# ControlBoard.net
KiCad netlist of a schematic drawn in EAGLE
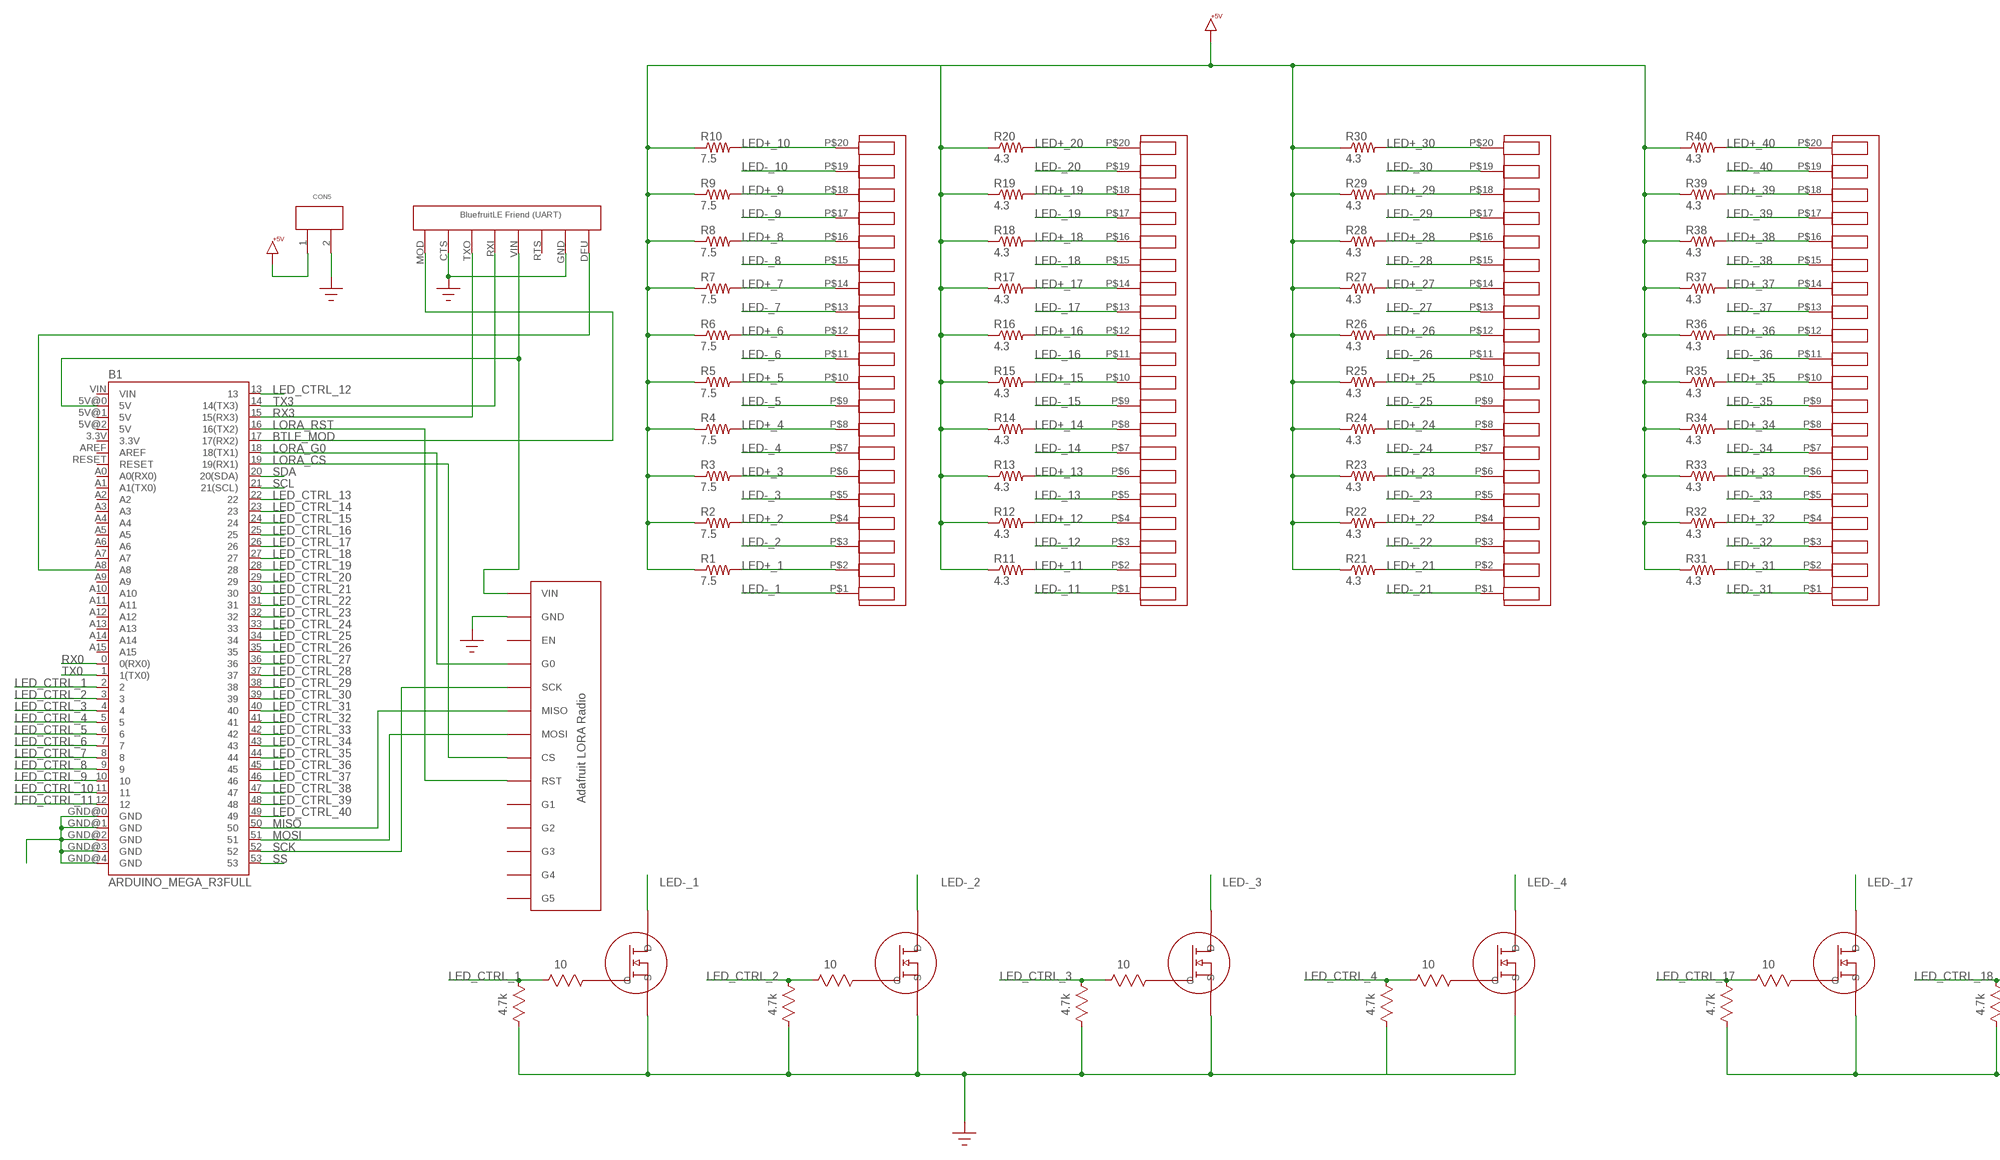
[diagram p0: schematic, sheet 1, part 1 of 3]
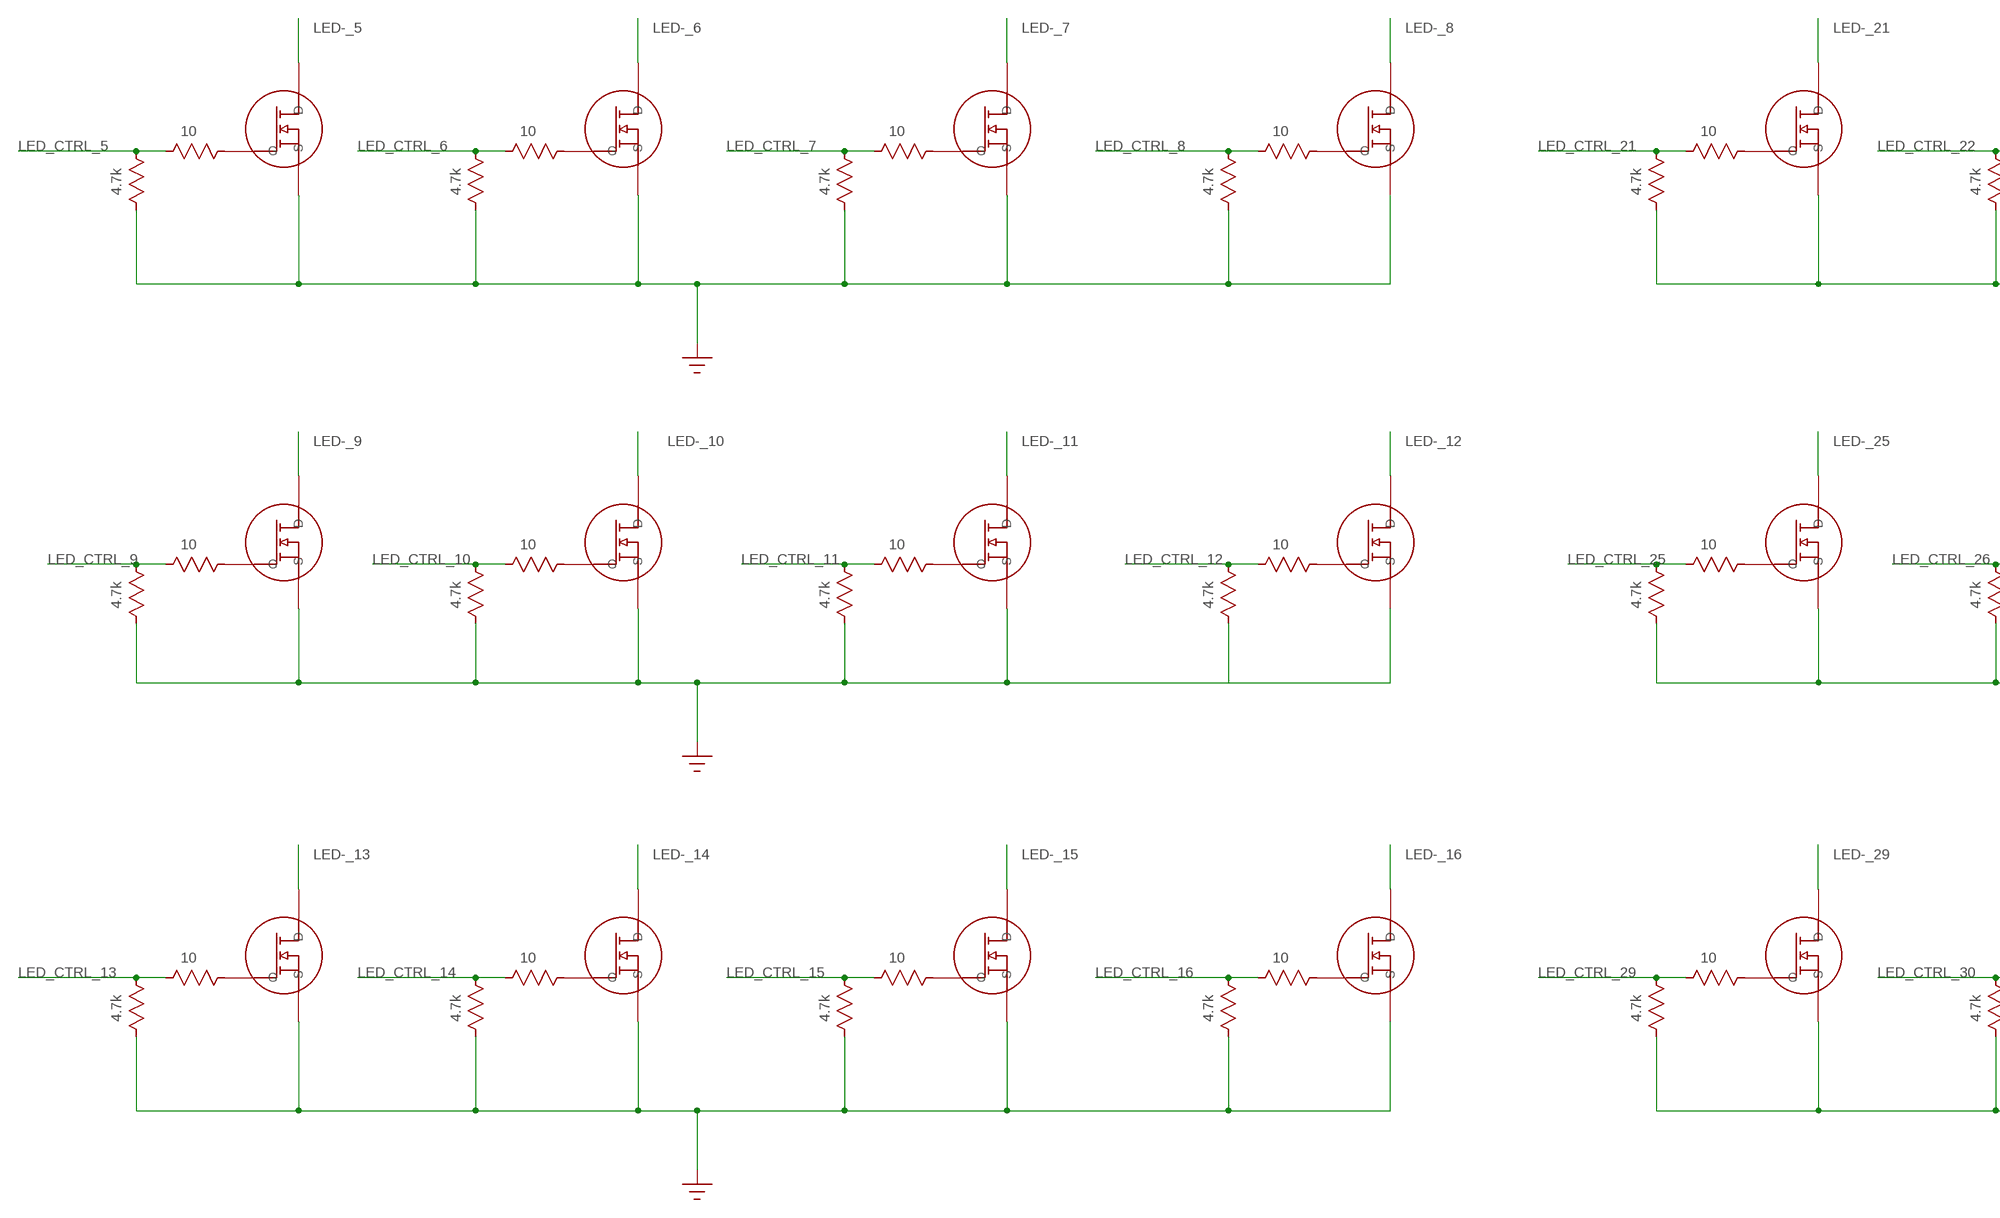
[diagram p1: schematic, sheet 1, part 2 of 3]
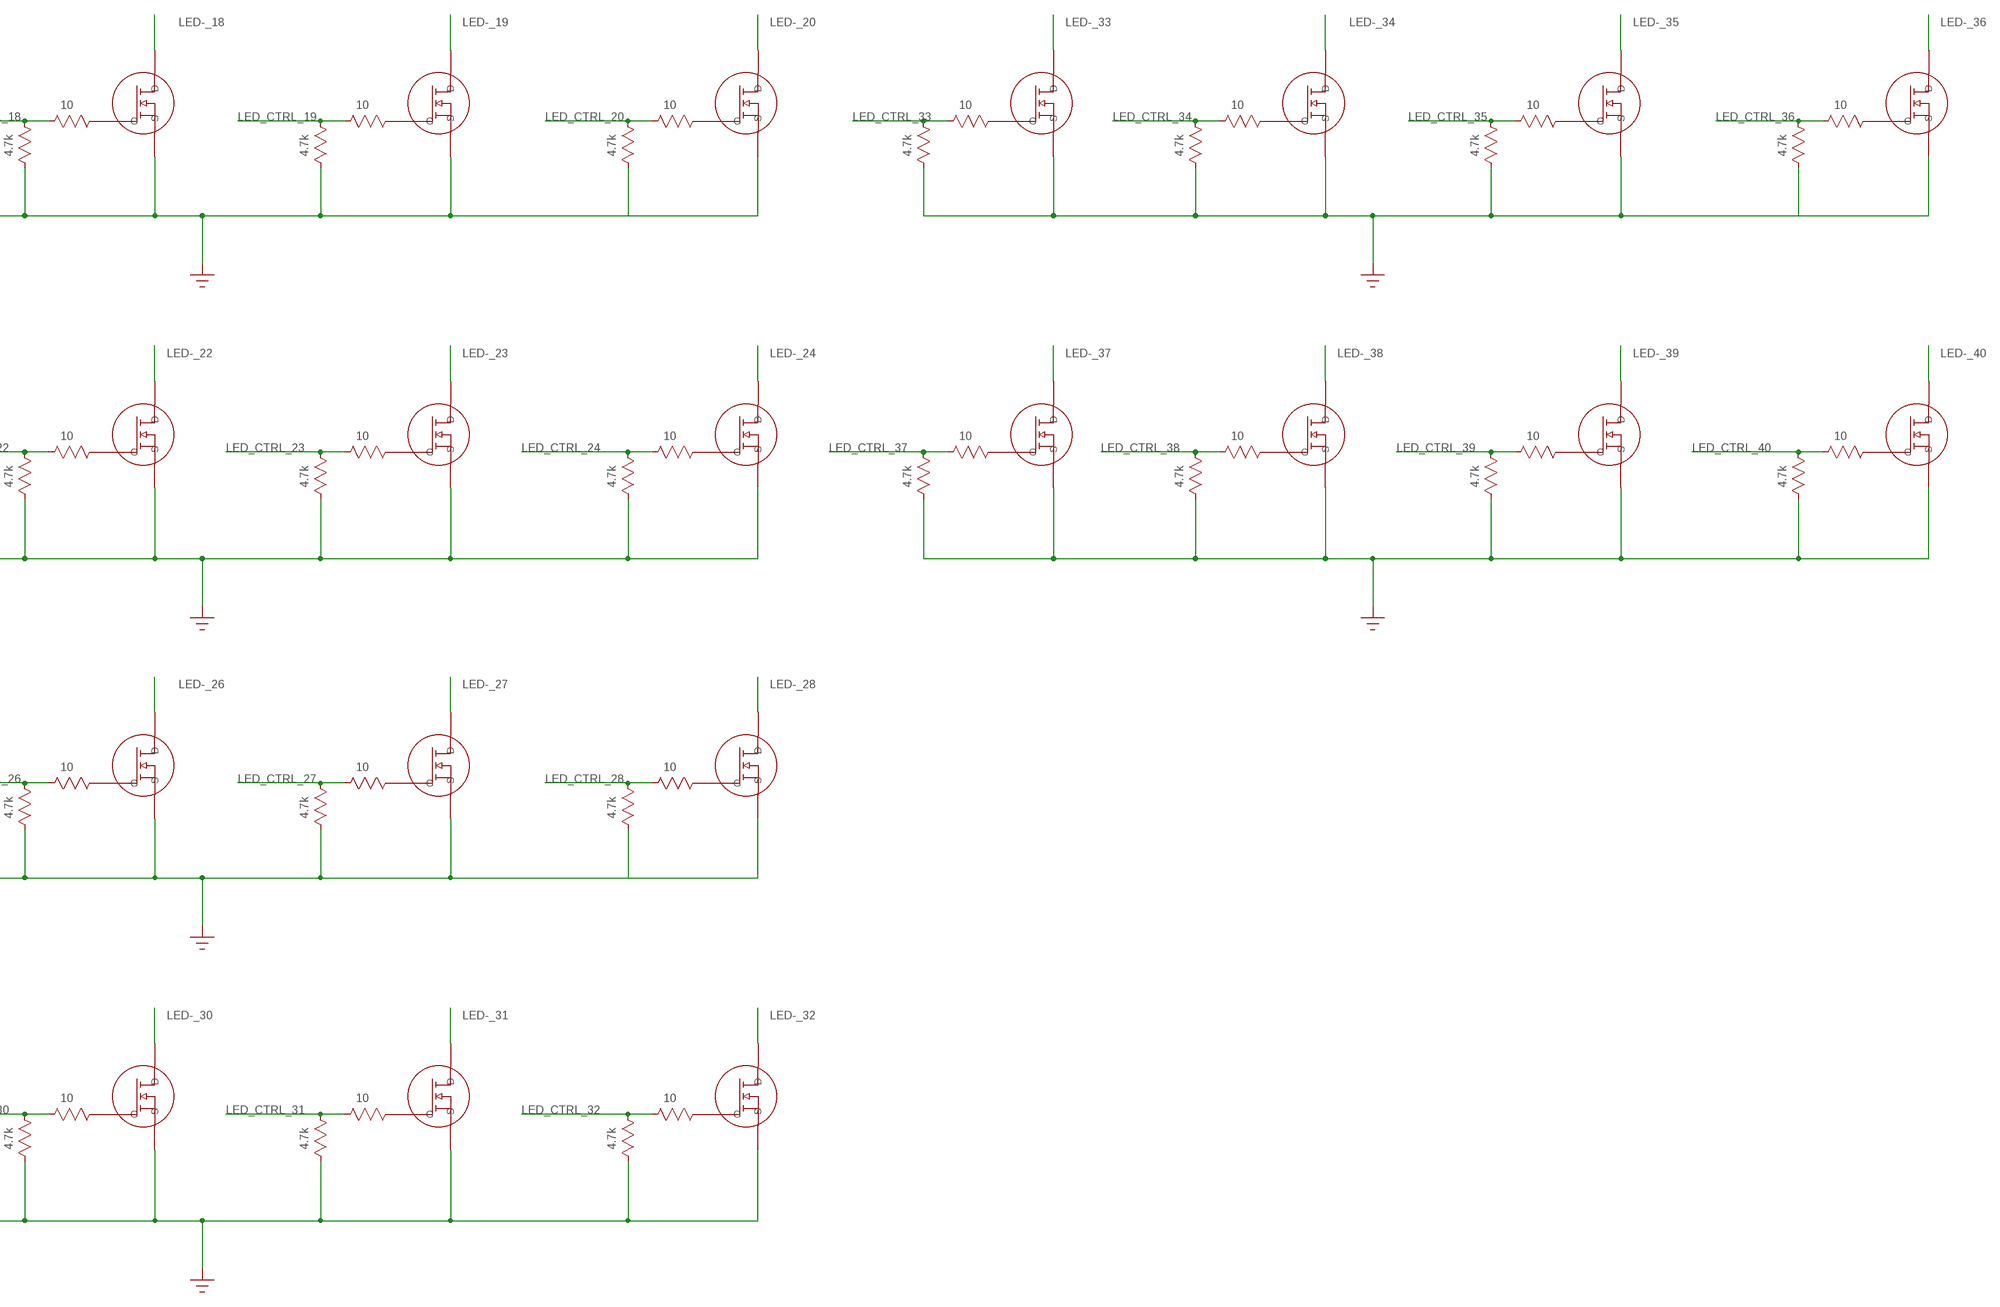
[diagram p2: schematic, sheet 1, part 3 of 3]

(export (version "E")
  (design (tool "Eeschema 10.0.6"))
  (components
    (comp (ref "B1")
      (value "ARDUINO_MEGA_R3FULL")
      (footprint "eagle-import:ARDUINO_MEGA")
      (libsource (lib "eagle-import") (part "ARDUINO_MEGA_R3FULL"))
    )
    (comp (ref "CON1")
      (value "CONN_20")
      (footprint "eagle-import:SPRING_CAGE_X20_1990180")
      (libsource (lib "eagle-import") (part "CONN_20"))
    )
    (comp (ref "CON2")
      (value "CONN_20")
      (footprint "eagle-import:SPRING_CAGE_X20_1990180")
      (libsource (lib "eagle-import") (part "CONN_20"))
    )
    (comp (ref "CON3")
      (value "CONN_20")
      (footprint "eagle-import:SPRING_CAGE_X20_1990180")
      (libsource (lib "eagle-import") (part "CONN_20"))
    )
    (comp (ref "CON4")
      (value "CONN_20")
      (footprint "eagle-import:SPRING_CAGE_X20_1990180")
      (libsource (lib "eagle-import") (part "CONN_20"))
    )
    (comp (ref "CON5")
      (value "CONN_2")
      (footprint "eagle-import:TERMINAL_BLOCK-2X_1792229")
      (libsource (lib "eagle-import") (part "CONN_2"))
    )
    (comp (ref "R1")
      (value "7.5")
      (footprint "eagle-import:RADIAL-RES-2W")
      (libsource (lib "eagle-import") (part "RESISTORPTH-2W_RADIAL"))
    )
    (comp (ref "R2")
      (value "7.5")
      (footprint "eagle-import:RADIAL-RES-2W")
      (libsource (lib "eagle-import") (part "RESISTORPTH-2W_RADIAL"))
    )
    (comp (ref "R3")
      (value "7.5")
      (footprint "eagle-import:RADIAL-RES-2W")
      (libsource (lib "eagle-import") (part "RESISTORPTH-2W_RADIAL"))
    )
    (comp (ref "R4")
      (value "7.5")
      (footprint "eagle-import:RADIAL-RES-2W")
      (libsource (lib "eagle-import") (part "RESISTORPTH-2W_RADIAL"))
    )
    (comp (ref "R5")
      (value "7.5")
      (footprint "eagle-import:RADIAL-RES-2W")
      (libsource (lib "eagle-import") (part "RESISTORPTH-2W_RADIAL"))
    )
    (comp (ref "R6")
      (value "7.5")
      (footprint "eagle-import:RADIAL-RES-2W")
      (libsource (lib "eagle-import") (part "RESISTORPTH-2W_RADIAL"))
    )
    (comp (ref "R7")
      (value "7.5")
      (footprint "eagle-import:RADIAL-RES-2W")
      (libsource (lib "eagle-import") (part "RESISTORPTH-2W_RADIAL"))
    )
    (comp (ref "R8")
      (value "7.5")
      (footprint "eagle-import:RADIAL-RES-2W")
      (libsource (lib "eagle-import") (part "RESISTORPTH-2W_RADIAL"))
    )
    (comp (ref "R9")
      (value "7.5")
      (footprint "eagle-import:RADIAL-RES-2W")
      (libsource (lib "eagle-import") (part "RESISTORPTH-2W_RADIAL"))
    )
    (comp (ref "R10")
      (value "7.5")
      (footprint "eagle-import:RADIAL-RES-2W")
      (libsource (lib "eagle-import") (part "RESISTORPTH-2W_RADIAL"))
    )
    (comp (ref "R11")
      (value "4.3")
      (footprint "eagle-import:RADIAL-RES-2W")
      (libsource (lib "eagle-import") (part "RESISTORPTH-2W_RADIAL"))
    )
    (comp (ref "R12")
      (value "4.3")
      (footprint "eagle-import:RADIAL-RES-2W")
      (libsource (lib "eagle-import") (part "RESISTORPTH-2W_RADIAL"))
    )
    (comp (ref "R13")
      (value "4.3")
      (footprint "eagle-import:RADIAL-RES-2W")
      (libsource (lib "eagle-import") (part "RESISTORPTH-2W_RADIAL"))
    )
    (comp (ref "R14")
      (value "4.3")
      (footprint "eagle-import:RADIAL-RES-2W")
      (libsource (lib "eagle-import") (part "RESISTORPTH-2W_RADIAL"))
    )
    (comp (ref "R15")
      (value "4.3")
      (footprint "eagle-import:RADIAL-RES-2W")
      (libsource (lib "eagle-import") (part "RESISTORPTH-2W_RADIAL"))
    )
    (comp (ref "R16")
      (value "4.3")
      (footprint "eagle-import:RADIAL-RES-2W")
      (libsource (lib "eagle-import") (part "RESISTORPTH-2W_RADIAL"))
    )
    (comp (ref "R17")
      (value "4.3")
      (footprint "eagle-import:RADIAL-RES-2W")
      (libsource (lib "eagle-import") (part "RESISTORPTH-2W_RADIAL"))
    )
    (comp (ref "R18")
      (value "4.3")
      (footprint "eagle-import:RADIAL-RES-2W")
      (libsource (lib "eagle-import") (part "RESISTORPTH-2W_RADIAL"))
    )
    (comp (ref "R19")
      (value "4.3")
      (footprint "eagle-import:RADIAL-RES-2W")
      (libsource (lib "eagle-import") (part "RESISTORPTH-2W_RADIAL"))
    )
    (comp (ref "R20")
      (value "4.3")
      (footprint "eagle-import:RADIAL-RES-2W")
      (libsource (lib "eagle-import") (part "RESISTORPTH-2W_RADIAL"))
    )
    (comp (ref "R21")
      (value "4.3")
      (footprint "eagle-import:RADIAL-RES-2W")
      (libsource (lib "eagle-import") (part "RESISTORPTH-2W_RADIAL"))
    )
    (comp (ref "R22")
      (value "4.3")
      (footprint "eagle-import:RADIAL-RES-2W")
      (libsource (lib "eagle-import") (part "RESISTORPTH-2W_RADIAL"))
    )
    (comp (ref "R23")
      (value "4.3")
      (footprint "eagle-import:RADIAL-RES-2W")
      (libsource (lib "eagle-import") (part "RESISTORPTH-2W_RADIAL"))
    )
    (comp (ref "R24")
      (value "4.3")
      (footprint "eagle-import:RADIAL-RES-2W")
      (libsource (lib "eagle-import") (part "RESISTORPTH-2W_RADIAL"))
    )
    (comp (ref "R25")
      (value "4.3")
      (footprint "eagle-import:RADIAL-RES-2W")
      (libsource (lib "eagle-import") (part "RESISTORPTH-2W_RADIAL"))
    )
    (comp (ref "R26")
      (value "4.3")
      (footprint "eagle-import:RADIAL-RES-2W")
      (libsource (lib "eagle-import") (part "RESISTORPTH-2W_RADIAL"))
    )
    (comp (ref "R27")
      (value "4.3")
      (footprint "eagle-import:RADIAL-RES-2W")
      (libsource (lib "eagle-import") (part "RESISTORPTH-2W_RADIAL"))
    )
    (comp (ref "R28")
      (value "4.3")
      (footprint "eagle-import:RADIAL-RES-2W")
      (libsource (lib "eagle-import") (part "RESISTORPTH-2W_RADIAL"))
    )
    (comp (ref "R29")
      (value "4.3")
      (footprint "eagle-import:RADIAL-RES-2W")
      (libsource (lib "eagle-import") (part "RESISTORPTH-2W_RADIAL"))
    )
    (comp (ref "R30")
      (value "4.3")
      (footprint "eagle-import:RADIAL-RES-2W")
      (libsource (lib "eagle-import") (part "RESISTORPTH-2W_RADIAL"))
    )
    (comp (ref "R31")
      (value "4.3")
      (footprint "eagle-import:RADIAL-RES-2W")
      (libsource (lib "eagle-import") (part "RESISTORPTH-2W_RADIAL"))
    )
    (comp (ref "R32")
      (value "4.3")
      (footprint "eagle-import:RADIAL-RES-2W")
      (libsource (lib "eagle-import") (part "RESISTORPTH-2W_RADIAL"))
    )
    (comp (ref "R33")
      (value "4.3")
      (footprint "eagle-import:RADIAL-RES-2W")
      (libsource (lib "eagle-import") (part "RESISTORPTH-2W_RADIAL"))
    )
    (comp (ref "R34")
      (value "4.3")
      (footprint "eagle-import:RADIAL-RES-2W")
      (libsource (lib "eagle-import") (part "RESISTORPTH-2W_RADIAL"))
    )
    (comp (ref "R35")
      (value "4.3")
      (footprint "eagle-import:RADIAL-RES-2W")
      (libsource (lib "eagle-import") (part "RESISTORPTH-2W_RADIAL"))
    )
    (comp (ref "R36")
      (value "4.3")
      (footprint "eagle-import:RADIAL-RES-2W")
      (libsource (lib "eagle-import") (part "RESISTORPTH-2W_RADIAL"))
    )
    (comp (ref "R37")
      (value "4.3")
      (footprint "eagle-import:RADIAL-RES-2W")
      (libsource (lib "eagle-import") (part "RESISTORPTH-2W_RADIAL"))
    )
    (comp (ref "R38")
      (value "4.3")
      (footprint "eagle-import:RADIAL-RES-2W")
      (libsource (lib "eagle-import") (part "RESISTORPTH-2W_RADIAL"))
    )
    (comp (ref "R39")
      (value "4.3")
      (footprint "eagle-import:RADIAL-RES-2W")
      (libsource (lib "eagle-import") (part "RESISTORPTH-2W_RADIAL"))
    )
    (comp (ref "R40")
      (value "4.3")
      (footprint "eagle-import:RADIAL-RES-2W")
      (libsource (lib "eagle-import") (part "RESISTORPTH-2W_RADIAL"))
    )
    (comp (ref "R41")
      (value "4.7k")
      (footprint "eagle-import:1506_X8")
      (libsource (lib "eagle-import") (part "RESISTOR_X8"))
    )
    (comp (ref "R42")
      (value "4.7k")
      (footprint "eagle-import:1506_X8")
      (libsource (lib "eagle-import") (part "RESISTOR_X8"))
    )
    (comp (ref "R43")
      (value "4.7k")
      (footprint "eagle-import:1506_X8")
      (libsource (lib "eagle-import") (part "RESISTOR_X8"))
    )
    (comp (ref "R44")
      (value "4.7k")
      (footprint "eagle-import:1506_X8")
      (libsource (lib "eagle-import") (part "RESISTOR_X8"))
    )
    (comp (ref "R45")
      (value "4.7k")
      (footprint "eagle-import:1506_X8")
      (libsource (lib "eagle-import") (part "RESISTOR_X8"))
    )
    (comp (ref "R46")
      (value "10")
      (footprint "eagle-import:1506_X8")
      (libsource (lib "eagle-import") (part "RESISTOR_X8"))
    )
    (comp (ref "R47")
      (value "10")
      (footprint "eagle-import:1506_X8")
      (libsource (lib "eagle-import") (part "RESISTOR_X8"))
    )
    (comp (ref "R48")
      (value "10")
      (footprint "eagle-import:1506_X8")
      (libsource (lib "eagle-import") (part "RESISTOR_X8"))
    )
    (comp (ref "R49")
      (value "10")
      (footprint "eagle-import:1506_X8")
      (libsource (lib "eagle-import") (part "RESISTOR_X8"))
    )
    (comp (ref "R50")
      (value "10")
      (footprint "eagle-import:1506_X8")
      (libsource (lib "eagle-import") (part "RESISTOR_X8"))
    )
    (comp (ref "U$1")
      (value "MOSFET")
      (footprint "eagle-import:SOT-23_TO-236")
      (libsource (lib "eagle-import") (part "MOSFET"))
    )
    (comp (ref "U$2")
      (value "MOSFET")
      (footprint "eagle-import:SOT-23_TO-236")
      (libsource (lib "eagle-import") (part "MOSFET"))
    )
    (comp (ref "U$3")
      (value "MOSFET")
      (footprint "eagle-import:SOT-23_TO-236")
      (libsource (lib "eagle-import") (part "MOSFET"))
    )
    (comp (ref "U$4")
      (value "MOSFET")
      (footprint "eagle-import:SOT-23_TO-236")
      (libsource (lib "eagle-import") (part "MOSFET"))
    )
    (comp (ref "U$5")
      (value "MOSFET")
      (footprint "eagle-import:SOT-23_TO-236")
      (libsource (lib "eagle-import") (part "MOSFET"))
    )
    (comp (ref "U$6")
      (value "MOSFET")
      (footprint "eagle-import:SOT-23_TO-236")
      (libsource (lib "eagle-import") (part "MOSFET"))
    )
    (comp (ref "U$7")
      (value "MOSFET")
      (footprint "eagle-import:SOT-23_TO-236")
      (libsource (lib "eagle-import") (part "MOSFET"))
    )
    (comp (ref "U$8")
      (value "MOSFET")
      (footprint "eagle-import:SOT-23_TO-236")
      (libsource (lib "eagle-import") (part "MOSFET"))
    )
    (comp (ref "U$9")
      (value "MOSFET")
      (footprint "eagle-import:SOT-23_TO-236")
      (libsource (lib "eagle-import") (part "MOSFET"))
    )
    (comp (ref "U$10")
      (value "MOSFET")
      (footprint "eagle-import:SOT-23_TO-236")
      (libsource (lib "eagle-import") (part "MOSFET"))
    )
    (comp (ref "U$15")
      (value "MOSFET")
      (footprint "eagle-import:SOT-23_TO-236")
      (libsource (lib "eagle-import") (part "MOSFET"))
    )
    (comp (ref "U$16")
      (value "MOSFET")
      (footprint "eagle-import:SOT-23_TO-236")
      (libsource (lib "eagle-import") (part "MOSFET"))
    )
    (comp (ref "U$17")
      (value "MOSFET")
      (footprint "eagle-import:SOT-23_TO-236")
      (libsource (lib "eagle-import") (part "MOSFET"))
    )
    (comp (ref "U$18")
      (value "MOSFET")
      (footprint "eagle-import:SOT-23_TO-236")
      (libsource (lib "eagle-import") (part "MOSFET"))
    )
    (comp (ref "U$19")
      (value "MOSFET")
      (footprint "eagle-import:SOT-23_TO-236")
      (libsource (lib "eagle-import") (part "MOSFET"))
    )
    (comp (ref "U$20")
      (value "MOSFET")
      (footprint "eagle-import:SOT-23_TO-236")
      (libsource (lib "eagle-import") (part "MOSFET"))
    )
    (comp (ref "U$21")
      (value "MOSFET")
      (footprint "eagle-import:SOT-23_TO-236")
      (libsource (lib "eagle-import") (part "MOSFET"))
    )
    (comp (ref "U$22")
      (value "MOSFET")
      (footprint "eagle-import:SOT-23_TO-236")
      (libsource (lib "eagle-import") (part "MOSFET"))
    )
    (comp (ref "U$27")
      (value "MOSFET")
      (footprint "eagle-import:SOT-23_TO-236")
      (libsource (lib "eagle-import") (part "MOSFET"))
    )
    (comp (ref "U$28")
      (value "MOSFET")
      (footprint "eagle-import:SOT-23_TO-236")
      (libsource (lib "eagle-import") (part "MOSFET"))
    )
    (comp (ref "U$29")
      (value "MOSFET")
      (footprint "eagle-import:SOT-23_TO-236")
      (libsource (lib "eagle-import") (part "MOSFET"))
    )
    (comp (ref "U$30")
      (value "MOSFET")
      (footprint "eagle-import:SOT-23_TO-236")
      (libsource (lib "eagle-import") (part "MOSFET"))
    )
    (comp (ref "U$31")
      (value "MOSFET")
      (footprint "eagle-import:SOT-23_TO-236")
      (libsource (lib "eagle-import") (part "MOSFET"))
    )
    (comp (ref "U$32")
      (value "MOSFET")
      (footprint "eagle-import:SOT-23_TO-236")
      (libsource (lib "eagle-import") (part "MOSFET"))
    )
    (comp (ref "U$37")
      (value "MOSFET")
      (footprint "eagle-import:SOT-23_TO-236")
      (libsource (lib "eagle-import") (part "MOSFET"))
    )
    (comp (ref "U$38")
      (value "MOSFET")
      (footprint "eagle-import:SOT-23_TO-236")
      (libsource (lib "eagle-import") (part "MOSFET"))
    )
    (comp (ref "U$39")
      (value "MOSFET")
      (footprint "eagle-import:SOT-23_TO-236")
      (libsource (lib "eagle-import") (part "MOSFET"))
    )
    (comp (ref "U$40")
      (value "MOSFET")
      (footprint "eagle-import:SOT-23_TO-236")
      (libsource (lib "eagle-import") (part "MOSFET"))
    )
    (comp (ref "U$41")
      (value "MOSFET")
      (footprint "eagle-import:SOT-23_TO-236")
      (libsource (lib "eagle-import") (part "MOSFET"))
    )
    (comp (ref "U$42")
      (value "MOSFET")
      (footprint "eagle-import:SOT-23_TO-236")
      (libsource (lib "eagle-import") (part "MOSFET"))
    )
    (comp (ref "U$43")
      (value "MOSFET")
      (footprint "eagle-import:SOT-23_TO-236")
      (libsource (lib "eagle-import") (part "MOSFET"))
    )
    (comp (ref "U$44")
      (value "MOSFET")
      (footprint "eagle-import:SOT-23_TO-236")
      (libsource (lib "eagle-import") (part "MOSFET"))
    )
    (comp (ref "U$49")
      (value "MOSFET")
      (footprint "eagle-import:SOT-23_TO-236")
      (libsource (lib "eagle-import") (part "MOSFET"))
    )
    (comp (ref "U$50")
      (value "MOSFET")
      (footprint "eagle-import:SOT-23_TO-236")
      (libsource (lib "eagle-import") (part "MOSFET"))
    )
    (comp (ref "U$51")
      (value "MOSFET")
      (footprint "eagle-import:SOT-23_TO-236")
      (libsource (lib "eagle-import") (part "MOSFET"))
    )
    (comp (ref "U$52")
      (value "MOSFET")
      (footprint "eagle-import:SOT-23_TO-236")
      (libsource (lib "eagle-import") (part "MOSFET"))
    )
    (comp (ref "U$53")
      (value "MOSFET")
      (footprint "eagle-import:SOT-23_TO-236")
      (libsource (lib "eagle-import") (part "MOSFET"))
    )
    (comp (ref "U$54")
      (value "MOSFET")
      (footprint "eagle-import:SOT-23_TO-236")
      (libsource (lib "eagle-import") (part "MOSFET"))
    )
    (comp (ref "U$55")
      (value "MOSFET")
      (footprint "eagle-import:SOT-23_TO-236")
      (libsource (lib "eagle-import") (part "MOSFET"))
    )
    (comp (ref "U$56")
      (value "MOSFET")
      (footprint "eagle-import:SOT-23_TO-236")
      (libsource (lib "eagle-import") (part "MOSFET"))
    )
    (comp (ref "U$62")
      (value "BLUEFRUIT_LE_FRIEND_UART")
      (footprint "eagle-import:BLUEFRUIT_LE_FRIEND_UART")
      (libsource (lib "eagle-import") (part "BLUEFRUIT_LE_FRIEND_UART"))
    )
    (comp (ref "U$64")
      (value "ADAFRUIT_LORA_RADIO")
      (footprint "eagle-import:ADAFRUIT_LORA_RADIO")
      (libsource (lib "eagle-import") (part "ADAFRUIT_LORA_RADIO"))
    )
  )
  (nets
    (net (code "1") (name "+5V") (class "Default")
      (node (ref "CON5") (pin "1") (pinfunction "P$1_1") (pintype "bidirectional"))
      (node (ref "R1") (pin "P$1") (pinfunction "1_P$1") (pintype "passive"))
      (node (ref "R10") (pin "P$1") (pinfunction "1_P$1") (pintype "passive"))
      (node (ref "R11") (pin "P$1") (pinfunction "1_P$1") (pintype "passive"))
      (node (ref "R12") (pin "P$1") (pinfunction "1_P$1") (pintype "passive"))
      (node (ref "R13") (pin "P$1") (pinfunction "1_P$1") (pintype "passive"))
      (node (ref "R14") (pin "P$1") (pinfunction "1_P$1") (pintype "passive"))
      (node (ref "R15") (pin "P$1") (pinfunction "1_P$1") (pintype "passive"))
      (node (ref "R16") (pin "P$1") (pinfunction "1_P$1") (pintype "passive"))
      (node (ref "R17") (pin "P$1") (pinfunction "1_P$1") (pintype "passive"))
      (node (ref "R18") (pin "P$1") (pinfunction "1_P$1") (pintype "passive"))
      (node (ref "R19") (pin "P$1") (pinfunction "1_P$1") (pintype "passive"))
      (node (ref "R2") (pin "P$1") (pinfunction "1_P$1") (pintype "passive"))
      (node (ref "R20") (pin "P$1") (pinfunction "1_P$1") (pintype "passive"))
      (node (ref "R21") (pin "P$1") (pinfunction "1_P$1") (pintype "passive"))
      (node (ref "R22") (pin "P$1") (pinfunction "1_P$1") (pintype "passive"))
      (node (ref "R23") (pin "P$1") (pinfunction "1_P$1") (pintype "passive"))
      (node (ref "R24") (pin "P$1") (pinfunction "1_P$1") (pintype "passive"))
      (node (ref "R25") (pin "P$1") (pinfunction "1_P$1") (pintype "passive"))
      (node (ref "R26") (pin "P$1") (pinfunction "1_P$1") (pintype "passive"))
      (node (ref "R27") (pin "P$1") (pinfunction "1_P$1") (pintype "passive"))
      (node (ref "R28") (pin "P$1") (pinfunction "1_P$1") (pintype "passive"))
      (node (ref "R29") (pin "P$1") (pinfunction "1_P$1") (pintype "passive"))
      (node (ref "R3") (pin "P$1") (pinfunction "1_P$1") (pintype "passive"))
      (node (ref "R30") (pin "P$1") (pinfunction "1_P$1") (pintype "passive"))
      (node (ref "R31") (pin "P$1") (pinfunction "1_P$1") (pintype "passive"))
      (node (ref "R32") (pin "P$1") (pinfunction "1_P$1") (pintype "passive"))
      (node (ref "R33") (pin "P$1") (pinfunction "1_P$1") (pintype "passive"))
      (node (ref "R34") (pin "P$1") (pinfunction "1_P$1") (pintype "passive"))
      (node (ref "R35") (pin "P$1") (pinfunction "1_P$1") (pintype "passive"))
      (node (ref "R36") (pin "P$1") (pinfunction "1_P$1") (pintype "passive"))
      (node (ref "R37") (pin "P$1") (pinfunction "1_P$1") (pintype "passive"))
      (node (ref "R38") (pin "P$1") (pinfunction "1_P$1") (pintype "passive"))
      (node (ref "R39") (pin "P$1") (pinfunction "1_P$1") (pintype "passive"))
      (node (ref "R4") (pin "P$1") (pinfunction "1_P$1") (pintype "passive"))
      (node (ref "R40") (pin "P$1") (pinfunction "1_P$1") (pintype "passive"))
      (node (ref "R5") (pin "P$1") (pinfunction "1_P$1") (pintype "passive"))
      (node (ref "R6") (pin "P$1") (pinfunction "1_P$1") (pintype "passive"))
      (node (ref "R7") (pin "P$1") (pinfunction "1_P$1") (pintype "passive"))
      (node (ref "R8") (pin "P$1") (pinfunction "1_P$1") (pintype "passive"))
      (node (ref "R9") (pin "P$1") (pinfunction "1_P$1") (pintype "passive"))
    )
    (net (code "2") (name "/BTLE_MOD") (class "Default")
      (node (ref "B1") (pin "17") (pinfunction "17(RX2)_17") (pintype "bidirectional"))
      (node (ref "U$62") (pin "MOD") (pinfunction "P$1_MOD") (pintype "bidirectional"))
    )
    (net (code "3") (name "/LED+_1") (class "Default")
      (node (ref "CON1") (pin "P$2") (pinfunction "2_P$2") (pintype "bidirectional"))
      (node (ref "R1") (pin "P$2") (pinfunction "2_P$2") (pintype "passive"))
    )
    (net (code "4") (name "/LED+_2") (class "Default")
      (node (ref "CON1") (pin "P$4") (pinfunction "4_P$4") (pintype "bidirectional"))
      (node (ref "R2") (pin "P$2") (pinfunction "2_P$2") (pintype "passive"))
    )
    (net (code "5") (name "/LED+_3") (class "Default")
      (node (ref "CON1") (pin "P$6") (pinfunction "6_P$6") (pintype "bidirectional"))
      (node (ref "R3") (pin "P$2") (pinfunction "2_P$2") (pintype "passive"))
    )
    (net (code "6") (name "/LED+_4") (class "Default")
      (node (ref "CON1") (pin "P$8") (pinfunction "8_P$8") (pintype "bidirectional"))
      (node (ref "R4") (pin "P$2") (pinfunction "2_P$2") (pintype "passive"))
    )
    (net (code "7") (name "/LED+_5") (class "Default")
      (node (ref "CON1") (pin "P$10") (pinfunction "10_P$10") (pintype "bidirectional"))
      (node (ref "R5") (pin "P$2") (pinfunction "2_P$2") (pintype "passive"))
    )
    (net (code "8") (name "/LED+_6") (class "Default")
      (node (ref "CON1") (pin "P$12") (pinfunction "12_P$12") (pintype "bidirectional"))
      (node (ref "R6") (pin "P$2") (pinfunction "2_P$2") (pintype "passive"))
    )
    (net (code "9") (name "/LED+_7") (class "Default")
      (node (ref "CON1") (pin "P$14") (pinfunction "14_P$14") (pintype "bidirectional"))
      (node (ref "R7") (pin "P$2") (pinfunction "2_P$2") (pintype "passive"))
    )
    (net (code "10") (name "/LED+_8") (class "Default")
      (node (ref "CON1") (pin "P$16") (pinfunction "16_P$16") (pintype "bidirectional"))
      (node (ref "R8") (pin "P$2") (pinfunction "2_P$2") (pintype "passive"))
    )
    (net (code "11") (name "/LED+_9") (class "Default")
      (node (ref "CON1") (pin "P$18") (pinfunction "18_P$18") (pintype "bidirectional"))
      (node (ref "R9") (pin "P$2") (pinfunction "2_P$2") (pintype "passive"))
    )
    (net (code "12") (name "/LED+_10") (class "Default")
      (node (ref "CON1") (pin "P$20") (pinfunction "20_P$20") (pintype "bidirectional"))
      (node (ref "R10") (pin "P$2") (pinfunction "2_P$2") (pintype "passive"))
    )
    (net (code "13") (name "/LED+_11") (class "Default")
      (node (ref "CON2") (pin "P$2") (pinfunction "2_P$2") (pintype "bidirectional"))
      (node (ref "R11") (pin "P$2") (pinfunction "2_P$2") (pintype "passive"))
    )
    (net (code "14") (name "/LED+_12") (class "Default")
      (node (ref "CON2") (pin "P$4") (pinfunction "4_P$4") (pintype "bidirectional"))
      (node (ref "R12") (pin "P$2") (pinfunction "2_P$2") (pintype "passive"))
    )
    (net (code "15") (name "/LED+_13") (class "Default")
      (node (ref "CON2") (pin "P$6") (pinfunction "6_P$6") (pintype "bidirectional"))
      (node (ref "R13") (pin "P$2") (pinfunction "2_P$2") (pintype "passive"))
    )
    (net (code "16") (name "/LED+_14") (class "Default")
      (node (ref "CON2") (pin "P$8") (pinfunction "8_P$8") (pintype "bidirectional"))
      (node (ref "R14") (pin "P$2") (pinfunction "2_P$2") (pintype "passive"))
    )
    (net (code "17") (name "/LED+_15") (class "Default")
      (node (ref "CON2") (pin "P$10") (pinfunction "10_P$10") (pintype "bidirectional"))
      (node (ref "R15") (pin "P$2") (pinfunction "2_P$2") (pintype "passive"))
    )
    (net (code "18") (name "/LED+_16") (class "Default")
      (node (ref "CON2") (pin "P$12") (pinfunction "12_P$12") (pintype "bidirectional"))
      (node (ref "R16") (pin "P$2") (pinfunction "2_P$2") (pintype "passive"))
    )
    (net (code "19") (name "/LED+_17") (class "Default")
      (node (ref "CON2") (pin "P$14") (pinfunction "14_P$14") (pintype "bidirectional"))
      (node (ref "R17") (pin "P$2") (pinfunction "2_P$2") (pintype "passive"))
    )
    (net (code "20") (name "/LED+_18") (class "Default")
      (node (ref "CON2") (pin "P$16") (pinfunction "16_P$16") (pintype "bidirectional"))
      (node (ref "R18") (pin "P$2") (pinfunction "2_P$2") (pintype "passive"))
    )
    (net (code "21") (name "/LED+_19") (class "Default")
      (node (ref "CON2") (pin "P$18") (pinfunction "18_P$18") (pintype "bidirectional"))
      (node (ref "R19") (pin "P$2") (pinfunction "2_P$2") (pintype "passive"))
    )
    (net (code "22") (name "/LED+_20") (class "Default")
      (node (ref "CON2") (pin "P$20") (pinfunction "20_P$20") (pintype "bidirectional"))
      (node (ref "R20") (pin "P$2") (pinfunction "2_P$2") (pintype "passive"))
    )
    (net (code "23") (name "/LED+_21") (class "Default")
      (node (ref "CON3") (pin "P$2") (pinfunction "2_P$2") (pintype "bidirectional"))
      (node (ref "R21") (pin "P$2") (pinfunction "2_P$2") (pintype "passive"))
    )
    (net (code "24") (name "/LED+_22") (class "Default")
      (node (ref "CON3") (pin "P$4") (pinfunction "4_P$4") (pintype "bidirectional"))
      (node (ref "R22") (pin "P$2") (pinfunction "2_P$2") (pintype "passive"))
    )
    (net (code "25") (name "/LED+_23") (class "Default")
      (node (ref "CON3") (pin "P$6") (pinfunction "6_P$6") (pintype "bidirectional"))
      (node (ref "R23") (pin "P$2") (pinfunction "2_P$2") (pintype "passive"))
    )
    (net (code "26") (name "/LED+_24") (class "Default")
      (node (ref "CON3") (pin "P$8") (pinfunction "8_P$8") (pintype "bidirectional"))
      (node (ref "R24") (pin "P$2") (pinfunction "2_P$2") (pintype "passive"))
    )
    (net (code "27") (name "/LED+_25") (class "Default")
      (node (ref "CON3") (pin "P$10") (pinfunction "10_P$10") (pintype "bidirectional"))
      (node (ref "R25") (pin "P$2") (pinfunction "2_P$2") (pintype "passive"))
    )
    (net (code "28") (name "/LED+_26") (class "Default")
      (node (ref "CON3") (pin "P$12") (pinfunction "12_P$12") (pintype "bidirectional"))
      (node (ref "R26") (pin "P$2") (pinfunction "2_P$2") (pintype "passive"))
    )
    (net (code "29") (name "/LED+_27") (class "Default")
      (node (ref "CON3") (pin "P$14") (pinfunction "14_P$14") (pintype "bidirectional"))
      (node (ref "R27") (pin "P$2") (pinfunction "2_P$2") (pintype "passive"))
    )
    (net (code "30") (name "/LED+_28") (class "Default")
      (node (ref "CON3") (pin "P$16") (pinfunction "16_P$16") (pintype "bidirectional"))
      (node (ref "R28") (pin "P$2") (pinfunction "2_P$2") (pintype "passive"))
    )
    (net (code "31") (name "/LED+_29") (class "Default")
      (node (ref "CON3") (pin "P$18") (pinfunction "18_P$18") (pintype "bidirectional"))
      (node (ref "R29") (pin "P$2") (pinfunction "2_P$2") (pintype "passive"))
    )
    (net (code "32") (name "/LED+_30") (class "Default")
      (node (ref "CON3") (pin "P$20") (pinfunction "20_P$20") (pintype "bidirectional"))
      (node (ref "R30") (pin "P$2") (pinfunction "2_P$2") (pintype "passive"))
    )
    (net (code "33") (name "/LED+_31") (class "Default")
      (node (ref "CON4") (pin "P$2") (pinfunction "2_P$2") (pintype "bidirectional"))
      (node (ref "R31") (pin "P$2") (pinfunction "2_P$2") (pintype "passive"))
    )
    (net (code "34") (name "/LED+_32") (class "Default")
      (node (ref "CON4") (pin "P$4") (pinfunction "4_P$4") (pintype "bidirectional"))
      (node (ref "R32") (pin "P$2") (pinfunction "2_P$2") (pintype "passive"))
    )
    (net (code "35") (name "/LED+_33") (class "Default")
      (node (ref "CON4") (pin "P$6") (pinfunction "6_P$6") (pintype "bidirectional"))
      (node (ref "R33") (pin "P$2") (pinfunction "2_P$2") (pintype "passive"))
    )
    (net (code "36") (name "/LED+_34") (class "Default")
      (node (ref "CON4") (pin "P$8") (pinfunction "8_P$8") (pintype "bidirectional"))
      (node (ref "R34") (pin "P$2") (pinfunction "2_P$2") (pintype "passive"))
    )
    (net (code "37") (name "/LED+_35") (class "Default")
      (node (ref "CON4") (pin "P$10") (pinfunction "10_P$10") (pintype "bidirectional"))
      (node (ref "R35") (pin "P$2") (pinfunction "2_P$2") (pintype "passive"))
    )
    (net (code "38") (name "/LED+_36") (class "Default")
      (node (ref "CON4") (pin "P$12") (pinfunction "12_P$12") (pintype "bidirectional"))
      (node (ref "R36") (pin "P$2") (pinfunction "2_P$2") (pintype "passive"))
    )
    (net (code "39") (name "/LED+_37") (class "Default")
      (node (ref "CON4") (pin "P$14") (pinfunction "14_P$14") (pintype "bidirectional"))
      (node (ref "R37") (pin "P$2") (pinfunction "2_P$2") (pintype "passive"))
    )
    (net (code "40") (name "/LED+_38") (class "Default")
      (node (ref "CON4") (pin "P$16") (pinfunction "16_P$16") (pintype "bidirectional"))
      (node (ref "R38") (pin "P$2") (pinfunction "2_P$2") (pintype "passive"))
    )
    (net (code "41") (name "/LED+_39") (class "Default")
      (node (ref "CON4") (pin "P$18") (pinfunction "18_P$18") (pintype "bidirectional"))
      (node (ref "R39") (pin "P$2") (pinfunction "2_P$2") (pintype "passive"))
    )
    (net (code "42") (name "/LED+_40") (class "Default")
      (node (ref "CON4") (pin "P$20") (pinfunction "20_P$20") (pintype "bidirectional"))
      (node (ref "R40") (pin "P$2") (pinfunction "2_P$2") (pintype "passive"))
    )
    (net (code "43") (name "/LED-_1") (class "Default")
      (node (ref "CON1") (pin "P$1") (pinfunction "1_P$1") (pintype "bidirectional"))
      (node (ref "U$3") (pin "P$3") (pinfunction "D_P$3") (pintype "input"))
    )
    (net (code "44") (name "/LED-_2") (class "Default")
      (node (ref "CON1") (pin "P$3") (pinfunction "3_P$3") (pintype "bidirectional"))
      (node (ref "U$4") (pin "P$3") (pinfunction "D_P$3") (pintype "input"))
    )
    (net (code "45") (name "/LED-_3") (class "Default")
      (node (ref "CON1") (pin "P$5") (pinfunction "5_P$5") (pintype "bidirectional"))
      (node (ref "U$5") (pin "P$3") (pinfunction "D_P$3") (pintype "input"))
    )
    (net (code "46") (name "/LED-_4") (class "Default")
      (node (ref "CON1") (pin "P$7") (pinfunction "7_P$7") (pintype "bidirectional"))
      (node (ref "U$6") (pin "P$3") (pinfunction "D_P$3") (pintype "input"))
    )
    (net (code "47") (name "/LED-_5") (class "Default")
      (node (ref "CON1") (pin "P$9") (pinfunction "9_P$9") (pintype "bidirectional"))
      (node (ref "U$7") (pin "P$3") (pinfunction "D_P$3") (pintype "input"))
    )
    (net (code "48") (name "/LED-_6") (class "Default")
      (node (ref "CON1") (pin "P$11") (pinfunction "11_P$11") (pintype "bidirectional"))
      (node (ref "U$8") (pin "P$3") (pinfunction "D_P$3") (pintype "input"))
    )
    (net (code "49") (name "/LED-_7") (class "Default")
      (node (ref "CON1") (pin "P$13") (pinfunction "13_P$13") (pintype "bidirectional"))
      (node (ref "U$9") (pin "P$3") (pinfunction "D_P$3") (pintype "input"))
    )
    (net (code "50") (name "/LED-_8") (class "Default")
      (node (ref "CON1") (pin "P$15") (pinfunction "15_P$15") (pintype "bidirectional"))
      (node (ref "U$10") (pin "P$3") (pinfunction "D_P$3") (pintype "input"))
    )
    (net (code "51") (name "/LED-_9") (class "Default")
      (node (ref "CON1") (pin "P$17") (pinfunction "17_P$17") (pintype "bidirectional"))
      (node (ref "U$15") (pin "P$3") (pinfunction "D_P$3") (pintype "input"))
    )
    (net (code "52") (name "/LED-_10") (class "Default")
      (node (ref "CON1") (pin "P$19") (pinfunction "19_P$19") (pintype "bidirectional"))
      (node (ref "U$16") (pin "P$3") (pinfunction "D_P$3") (pintype "input"))
    )
    (net (code "53") (name "/LED-_11") (class "Default")
      (node (ref "CON2") (pin "P$1") (pinfunction "1_P$1") (pintype "bidirectional"))
      (node (ref "U$17") (pin "P$3") (pinfunction "D_P$3") (pintype "input"))
    )
    (net (code "54") (name "/LED-_12") (class "Default")
      (node (ref "CON2") (pin "P$3") (pinfunction "3_P$3") (pintype "bidirectional"))
      (node (ref "U$18") (pin "P$3") (pinfunction "D_P$3") (pintype "input"))
    )
    (net (code "55") (name "/LED-_13") (class "Default")
      (node (ref "CON2") (pin "P$5") (pinfunction "5_P$5") (pintype "bidirectional"))
      (node (ref "U$19") (pin "P$3") (pinfunction "D_P$3") (pintype "input"))
    )
    (net (code "56") (name "/LED-_14") (class "Default")
      (node (ref "CON2") (pin "P$7") (pinfunction "7_P$7") (pintype "bidirectional"))
      (node (ref "U$20") (pin "P$3") (pinfunction "D_P$3") (pintype "input"))
    )
    (net (code "57") (name "/LED-_15") (class "Default")
      (node (ref "CON2") (pin "P$9") (pinfunction "9_P$9") (pintype "bidirectional"))
      (node (ref "U$21") (pin "P$3") (pinfunction "D_P$3") (pintype "input"))
    )
    (net (code "58") (name "/LED-_16") (class "Default")
      (node (ref "CON2") (pin "P$11") (pinfunction "11_P$11") (pintype "bidirectional"))
      (node (ref "U$22") (pin "P$3") (pinfunction "D_P$3") (pintype "input"))
    )
    (net (code "59") (name "/LED-_17") (class "Default")
      (node (ref "CON2") (pin "P$13") (pinfunction "13_P$13") (pintype "bidirectional"))
      (node (ref "U$1") (pin "P$3") (pinfunction "D_P$3") (pintype "input"))
    )
    (net (code "60") (name "/LED-_18") (class "Default")
      (node (ref "CON2") (pin "P$15") (pinfunction "15_P$15") (pintype "bidirectional"))
      (node (ref "U$2") (pin "P$3") (pinfunction "D_P$3") (pintype "input"))
    )
    (net (code "61") (name "/LED-_19") (class "Default")
      (node (ref "CON2") (pin "P$17") (pinfunction "17_P$17") (pintype "bidirectional"))
      (node (ref "U$27") (pin "P$3") (pinfunction "D_P$3") (pintype "input"))
    )
    (net (code "62") (name "/LED-_20") (class "Default")
      (node (ref "CON2") (pin "P$19") (pinfunction "19_P$19") (pintype "bidirectional"))
      (node (ref "U$28") (pin "P$3") (pinfunction "D_P$3") (pintype "input"))
    )
    (net (code "63") (name "/LED-_21") (class "Default")
      (node (ref "CON3") (pin "P$1") (pinfunction "1_P$1") (pintype "bidirectional"))
      (node (ref "U$29") (pin "P$3") (pinfunction "D_P$3") (pintype "input"))
    )
    (net (code "64") (name "/LED-_22") (class "Default")
      (node (ref "CON3") (pin "P$3") (pinfunction "3_P$3") (pintype "bidirectional"))
      (node (ref "U$30") (pin "P$3") (pinfunction "D_P$3") (pintype "input"))
    )
    (net (code "65") (name "/LED-_23") (class "Default")
      (node (ref "CON3") (pin "P$5") (pinfunction "5_P$5") (pintype "bidirectional"))
      (node (ref "U$31") (pin "P$3") (pinfunction "D_P$3") (pintype "input"))
    )
    (net (code "66") (name "/LED-_24") (class "Default")
      (node (ref "CON3") (pin "P$7") (pinfunction "7_P$7") (pintype "bidirectional"))
      (node (ref "U$32") (pin "P$3") (pinfunction "D_P$3") (pintype "input"))
    )
    (net (code "67") (name "/LED-_25") (class "Default")
      (node (ref "CON3") (pin "P$9") (pinfunction "9_P$9") (pintype "bidirectional"))
      (node (ref "U$37") (pin "P$3") (pinfunction "D_P$3") (pintype "input"))
    )
    (net (code "68") (name "/LED-_26") (class "Default")
      (node (ref "CON3") (pin "P$11") (pinfunction "11_P$11") (pintype "bidirectional"))
      (node (ref "U$38") (pin "P$3") (pinfunction "D_P$3") (pintype "input"))
    )
    (net (code "69") (name "/LED-_27") (class "Default")
      (node (ref "CON3") (pin "P$13") (pinfunction "13_P$13") (pintype "bidirectional"))
      (node (ref "U$39") (pin "P$3") (pinfunction "D_P$3") (pintype "input"))
    )
    (net (code "70") (name "/LED-_28") (class "Default")
      (node (ref "CON3") (pin "P$15") (pinfunction "15_P$15") (pintype "bidirectional"))
      (node (ref "U$40") (pin "P$3") (pinfunction "D_P$3") (pintype "input"))
    )
    (net (code "71") (name "/LED-_29") (class "Default")
      (node (ref "CON3") (pin "P$17") (pinfunction "17_P$17") (pintype "bidirectional"))
      (node (ref "U$41") (pin "P$3") (pinfunction "D_P$3") (pintype "input"))
    )
    (net (code "72") (name "/LED-_30") (class "Default")
      (node (ref "CON3") (pin "P$19") (pinfunction "19_P$19") (pintype "bidirectional"))
      (node (ref "U$42") (pin "P$3") (pinfunction "D_P$3") (pintype "input"))
    )
    (net (code "73") (name "/LED-_31") (class "Default")
      (node (ref "CON4") (pin "P$1") (pinfunction "1_P$1") (pintype "bidirectional"))
      (node (ref "U$43") (pin "P$3") (pinfunction "D_P$3") (pintype "input"))
    )
    (net (code "74") (name "/LED-_32") (class "Default")
      (node (ref "CON4") (pin "P$3") (pinfunction "3_P$3") (pintype "bidirectional"))
      (node (ref "U$44") (pin "P$3") (pinfunction "D_P$3") (pintype "input"))
    )
    (net (code "75") (name "/LED-_33") (class "Default")
      (node (ref "CON4") (pin "P$5") (pinfunction "5_P$5") (pintype "bidirectional"))
      (node (ref "U$49") (pin "P$3") (pinfunction "D_P$3") (pintype "input"))
    )
    (net (code "76") (name "/LED-_34") (class "Default")
      (node (ref "CON4") (pin "P$7") (pinfunction "7_P$7") (pintype "bidirectional"))
      (node (ref "U$50") (pin "P$3") (pinfunction "D_P$3") (pintype "input"))
    )
    (net (code "77") (name "/LED-_35") (class "Default")
      (node (ref "CON4") (pin "P$9") (pinfunction "9_P$9") (pintype "bidirectional"))
      (node (ref "U$51") (pin "P$3") (pinfunction "D_P$3") (pintype "input"))
    )
    (net (code "78") (name "/LED-_36") (class "Default")
      (node (ref "CON4") (pin "P$11") (pinfunction "11_P$11") (pintype "bidirectional"))
      (node (ref "U$52") (pin "P$3") (pinfunction "D_P$3") (pintype "input"))
    )
    (net (code "79") (name "/LED-_37") (class "Default")
      (node (ref "CON4") (pin "P$13") (pinfunction "13_P$13") (pintype "bidirectional"))
      (node (ref "U$53") (pin "P$3") (pinfunction "D_P$3") (pintype "input"))
    )
    (net (code "80") (name "/LED-_38") (class "Default")
      (node (ref "CON4") (pin "P$15") (pinfunction "15_P$15") (pintype "bidirectional"))
      (node (ref "U$54") (pin "P$3") (pinfunction "D_P$3") (pintype "input"))
    )
    (net (code "81") (name "/LED-_39") (class "Default")
      (node (ref "CON4") (pin "P$17") (pinfunction "17_P$17") (pintype "bidirectional"))
      (node (ref "U$55") (pin "P$3") (pinfunction "D_P$3") (pintype "input"))
    )
    (net (code "82") (name "/LED-_40") (class "Default")
      (node (ref "CON4") (pin "P$19") (pinfunction "19_P$19") (pintype "bidirectional"))
      (node (ref "U$56") (pin "P$3") (pinfunction "D_P$3") (pintype "input"))
    )
    (net (code "83") (name "/LED_CTRL_1") (class "Default")
      (node (ref "B1") (pin "2") (pinfunction "2_2") (pintype "bidirectional"))
      (node (ref "R41") (pin "P$16") (pinfunction "P$2_P$16") (pintype "passive"))
      (node (ref "R46") (pin "P$1") (pinfunction "P$1_P$1") (pintype "passive"))
    )
    (net (code "84") (name "/LED_CTRL_2") (class "Default")
      (node (ref "B1") (pin "3") (pinfunction "3_3") (pintype "bidirectional"))
      (node (ref "R41") (pin "P$15") (pinfunction "P$2_P$15") (pintype "passive"))
      (node (ref "R46") (pin "P$2") (pinfunction "P$1_P$2") (pintype "passive"))
    )
    (net (code "85") (name "/LED_CTRL_3") (class "Default")
      (node (ref "B1") (pin "4") (pinfunction "4_4") (pintype "bidirectional"))
      (node (ref "R41") (pin "P$14") (pinfunction "P$2_P$14") (pintype "passive"))
      (node (ref "R46") (pin "P$3") (pinfunction "P$1_P$3") (pintype "passive"))
    )
    (net (code "86") (name "/LED_CTRL_4") (class "Default")
      (node (ref "B1") (pin "5") (pinfunction "5_5") (pintype "bidirectional"))
      (node (ref "R41") (pin "P$13") (pinfunction "P$2_P$13") (pintype "passive"))
      (node (ref "R46") (pin "P$4") (pinfunction "P$1_P$4") (pintype "passive"))
    )
    (net (code "87") (name "/LED_CTRL_5") (class "Default")
      (node (ref "B1") (pin "6") (pinfunction "6_6") (pintype "bidirectional"))
      (node (ref "R41") (pin "P$12") (pinfunction "P$2_P$12") (pintype "passive"))
      (node (ref "R46") (pin "P$5") (pinfunction "P$1_P$5") (pintype "passive"))
    )
    (net (code "88") (name "/LED_CTRL_6") (class "Default")
      (node (ref "B1") (pin "7") (pinfunction "7_7") (pintype "bidirectional"))
      (node (ref "R41") (pin "P$11") (pinfunction "P$2_P$11") (pintype "passive"))
      (node (ref "R46") (pin "P$6") (pinfunction "P$1_P$6") (pintype "passive"))
    )
    (net (code "89") (name "/LED_CTRL_7") (class "Default")
      (node (ref "B1") (pin "8") (pinfunction "8_8") (pintype "bidirectional"))
      (node (ref "R41") (pin "P$10") (pinfunction "P$2_P$10") (pintype "passive"))
      (node (ref "R46") (pin "P$7") (pinfunction "P$1_P$7") (pintype "passive"))
    )
    (net (code "90") (name "/LED_CTRL_8") (class "Default")
      (node (ref "B1") (pin "9") (pinfunction "9_9") (pintype "bidirectional"))
      (node (ref "R41") (pin "P$9") (pinfunction "P$2_P$9") (pintype "passive"))
      (node (ref "R46") (pin "P$8") (pinfunction "P$1_P$8") (pintype "passive"))
    )
    (net (code "91") (name "/LED_CTRL_9") (class "Default")
      (node (ref "B1") (pin "10") (pinfunction "10_10") (pintype "bidirectional"))
      (node (ref "R42") (pin "P$16") (pinfunction "P$2_P$16") (pintype "passive"))
      (node (ref "R47") (pin "P$1") (pinfunction "P$1_P$1") (pintype "passive"))
    )
    (net (code "92") (name "/LED_CTRL_10") (class "Default")
      (node (ref "B1") (pin "11") (pinfunction "11_11") (pintype "bidirectional"))
      (node (ref "R42") (pin "P$15") (pinfunction "P$2_P$15") (pintype "passive"))
      (node (ref "R47") (pin "P$2") (pinfunction "P$1_P$2") (pintype "passive"))
    )
    (net (code "93") (name "/LED_CTRL_11") (class "Default")
      (node (ref "B1") (pin "12") (pinfunction "12_12") (pintype "bidirectional"))
      (node (ref "R42") (pin "P$14") (pinfunction "P$2_P$14") (pintype "passive"))
      (node (ref "R47") (pin "P$3") (pinfunction "P$1_P$3") (pintype "passive"))
    )
    (net (code "94") (name "/LED_CTRL_12") (class "Default")
      (node (ref "B1") (pin "13") (pinfunction "13_13") (pintype "bidirectional"))
      (node (ref "R42") (pin "P$13") (pinfunction "P$2_P$13") (pintype "passive"))
      (node (ref "R47") (pin "P$4") (pinfunction "P$1_P$4") (pintype "passive"))
    )
    (net (code "95") (name "/LED_CTRL_13") (class "Default")
      (node (ref "B1") (pin "22") (pinfunction "22_22") (pintype "bidirectional"))
      (node (ref "R42") (pin "P$12") (pinfunction "P$2_P$12") (pintype "passive"))
      (node (ref "R47") (pin "P$5") (pinfunction "P$1_P$5") (pintype "passive"))
    )
    (net (code "96") (name "/LED_CTRL_14") (class "Default")
      (node (ref "B1") (pin "23") (pinfunction "23_23") (pintype "bidirectional"))
      (node (ref "R42") (pin "P$11") (pinfunction "P$2_P$11") (pintype "passive"))
      (node (ref "R47") (pin "P$6") (pinfunction "P$1_P$6") (pintype "passive"))
    )
    (net (code "97") (name "/LED_CTRL_15") (class "Default")
      (node (ref "B1") (pin "24") (pinfunction "24_24") (pintype "bidirectional"))
      (node (ref "R42") (pin "P$10") (pinfunction "P$2_P$10") (pintype "passive"))
      (node (ref "R47") (pin "P$7") (pinfunction "P$1_P$7") (pintype "passive"))
    )
    (net (code "98") (name "/LED_CTRL_16") (class "Default")
      (node (ref "B1") (pin "25") (pinfunction "25_25") (pintype "bidirectional"))
      (node (ref "R42") (pin "P$9") (pinfunction "P$2_P$9") (pintype "passive"))
      (node (ref "R47") (pin "P$8") (pinfunction "P$1_P$8") (pintype "passive"))
    )
    (net (code "99") (name "/LED_CTRL_17") (class "Default")
      (node (ref "B1") (pin "26") (pinfunction "26_26") (pintype "bidirectional"))
      (node (ref "R43") (pin "P$16") (pinfunction "P$2_P$16") (pintype "passive"))
      (node (ref "R48") (pin "P$1") (pinfunction "P$1_P$1") (pintype "passive"))
    )
    (net (code "100") (name "/LED_CTRL_18") (class "Default")
      (node (ref "B1") (pin "27") (pinfunction "27_27") (pintype "bidirectional"))
      (node (ref "R43") (pin "P$15") (pinfunction "P$2_P$15") (pintype "passive"))
      (node (ref "R48") (pin "P$2") (pinfunction "P$1_P$2") (pintype "passive"))
    )
    (net (code "101") (name "/LED_CTRL_19") (class "Default")
      (node (ref "B1") (pin "28") (pinfunction "28_28") (pintype "bidirectional"))
      (node (ref "R43") (pin "P$14") (pinfunction "P$2_P$14") (pintype "passive"))
      (node (ref "R48") (pin "P$3") (pinfunction "P$1_P$3") (pintype "passive"))
    )
    (net (code "102") (name "/LED_CTRL_20") (class "Default")
      (node (ref "B1") (pin "29") (pinfunction "29_29") (pintype "bidirectional"))
      (node (ref "R43") (pin "P$13") (pinfunction "P$2_P$13") (pintype "passive"))
      (node (ref "R48") (pin "P$4") (pinfunction "P$1_P$4") (pintype "passive"))
    )
    (net (code "103") (name "/LED_CTRL_21") (class "Default")
      (node (ref "B1") (pin "30") (pinfunction "30_30") (pintype "bidirectional"))
      (node (ref "R43") (pin "P$12") (pinfunction "P$2_P$12") (pintype "passive"))
      (node (ref "R48") (pin "P$5") (pinfunction "P$1_P$5") (pintype "passive"))
    )
    (net (code "104") (name "/LED_CTRL_22") (class "Default")
      (node (ref "B1") (pin "31") (pinfunction "31_31") (pintype "bidirectional"))
      (node (ref "R43") (pin "P$11") (pinfunction "P$2_P$11") (pintype "passive"))
      (node (ref "R48") (pin "P$6") (pinfunction "P$1_P$6") (pintype "passive"))
    )
    (net (code "105") (name "/LED_CTRL_23") (class "Default")
      (node (ref "B1") (pin "32") (pinfunction "32_32") (pintype "bidirectional"))
      (node (ref "R43") (pin "P$10") (pinfunction "P$2_P$10") (pintype "passive"))
      (node (ref "R48") (pin "P$7") (pinfunction "P$1_P$7") (pintype "passive"))
    )
    (net (code "106") (name "/LED_CTRL_24") (class "Default")
      (node (ref "B1") (pin "33") (pinfunction "33_33") (pintype "bidirectional"))
      (node (ref "R43") (pin "P$9") (pinfunction "P$2_P$9") (pintype "passive"))
      (node (ref "R48") (pin "P$8") (pinfunction "P$1_P$8") (pintype "passive"))
    )
    (net (code "107") (name "/LED_CTRL_25") (class "Default")
      (node (ref "B1") (pin "34") (pinfunction "34_34") (pintype "bidirectional"))
      (node (ref "R44") (pin "P$16") (pinfunction "P$2_P$16") (pintype "passive"))
      (node (ref "R49") (pin "P$1") (pinfunction "P$1_P$1") (pintype "passive"))
    )
    (net (code "108") (name "/LED_CTRL_26") (class "Default")
      (node (ref "B1") (pin "35") (pinfunction "35_35") (pintype "bidirectional"))
      (node (ref "R44") (pin "P$15") (pinfunction "P$2_P$15") (pintype "passive"))
      (node (ref "R49") (pin "P$2") (pinfunction "P$1_P$2") (pintype "passive"))
    )
    (net (code "109") (name "/LED_CTRL_27") (class "Default")
      (node (ref "B1") (pin "36") (pinfunction "36_36") (pintype "bidirectional"))
      (node (ref "R44") (pin "P$14") (pinfunction "P$2_P$14") (pintype "passive"))
      (node (ref "R49") (pin "P$3") (pinfunction "P$1_P$3") (pintype "passive"))
    )
    (net (code "110") (name "/LED_CTRL_28") (class "Default")
      (node (ref "B1") (pin "37") (pinfunction "37_37") (pintype "bidirectional"))
      (node (ref "R44") (pin "P$13") (pinfunction "P$2_P$13") (pintype "passive"))
      (node (ref "R49") (pin "P$4") (pinfunction "P$1_P$4") (pintype "passive"))
    )
    (net (code "111") (name "/LED_CTRL_29") (class "Default")
      (node (ref "B1") (pin "38") (pinfunction "38_38") (pintype "bidirectional"))
      (node (ref "R44") (pin "P$12") (pinfunction "P$2_P$12") (pintype "passive"))
      (node (ref "R49") (pin "P$5") (pinfunction "P$1_P$5") (pintype "passive"))
    )
    (net (code "112") (name "/LED_CTRL_30") (class "Default")
      (node (ref "B1") (pin "39") (pinfunction "39_39") (pintype "bidirectional"))
      (node (ref "R44") (pin "P$11") (pinfunction "P$2_P$11") (pintype "passive"))
      (node (ref "R49") (pin "P$6") (pinfunction "P$1_P$6") (pintype "passive"))
    )
    (net (code "113") (name "/LED_CTRL_31") (class "Default")
      (node (ref "B1") (pin "40") (pinfunction "40_40") (pintype "bidirectional"))
      (node (ref "R44") (pin "P$10") (pinfunction "P$2_P$10") (pintype "passive"))
      (node (ref "R49") (pin "P$7") (pinfunction "P$1_P$7") (pintype "passive"))
    )
    (net (code "114") (name "/LED_CTRL_32") (class "Default")
      (node (ref "B1") (pin "41") (pinfunction "41_41") (pintype "bidirectional"))
      (node (ref "R44") (pin "P$9") (pinfunction "P$2_P$9") (pintype "passive"))
      (node (ref "R49") (pin "P$8") (pinfunction "P$1_P$8") (pintype "passive"))
    )
    (net (code "115") (name "/LED_CTRL_33") (class "Default")
      (node (ref "B1") (pin "42") (pinfunction "42_42") (pintype "bidirectional"))
      (node (ref "R45") (pin "P$16") (pinfunction "P$2_P$16") (pintype "passive"))
      (node (ref "R50") (pin "P$1") (pinfunction "P$1_P$1") (pintype "passive"))
    )
    (net (code "116") (name "/LED_CTRL_34") (class "Default")
      (node (ref "B1") (pin "43") (pinfunction "43_43") (pintype "bidirectional"))
      (node (ref "R45") (pin "P$15") (pinfunction "P$2_P$15") (pintype "passive"))
      (node (ref "R50") (pin "P$2") (pinfunction "P$1_P$2") (pintype "passive"))
    )
    (net (code "117") (name "/LED_CTRL_35") (class "Default")
      (node (ref "B1") (pin "44") (pinfunction "44_44") (pintype "bidirectional"))
      (node (ref "R45") (pin "P$14") (pinfunction "P$2_P$14") (pintype "passive"))
      (node (ref "R50") (pin "P$3") (pinfunction "P$1_P$3") (pintype "passive"))
    )
    (net (code "118") (name "/LED_CTRL_36") (class "Default")
      (node (ref "B1") (pin "45") (pinfunction "45_45") (pintype "bidirectional"))
      (node (ref "R45") (pin "P$13") (pinfunction "P$2_P$13") (pintype "passive"))
      (node (ref "R50") (pin "P$4") (pinfunction "P$1_P$4") (pintype "passive"))
    )
    (net (code "119") (name "/LED_CTRL_37") (class "Default")
      (node (ref "B1") (pin "46") (pinfunction "46_46") (pintype "bidirectional"))
      (node (ref "R45") (pin "P$12") (pinfunction "P$2_P$12") (pintype "passive"))
      (node (ref "R50") (pin "P$5") (pinfunction "P$1_P$5") (pintype "passive"))
    )
    (net (code "120") (name "/LED_CTRL_38") (class "Default")
      (node (ref "B1") (pin "47") (pinfunction "47_47") (pintype "bidirectional"))
      (node (ref "R45") (pin "P$11") (pinfunction "P$2_P$11") (pintype "passive"))
      (node (ref "R50") (pin "P$6") (pinfunction "P$1_P$6") (pintype "passive"))
    )
    (net (code "121") (name "/LED_CTRL_39") (class "Default")
      (node (ref "B1") (pin "48") (pinfunction "48_48") (pintype "bidirectional"))
      (node (ref "R45") (pin "P$10") (pinfunction "P$2_P$10") (pintype "passive"))
      (node (ref "R50") (pin "P$7") (pinfunction "P$1_P$7") (pintype "passive"))
    )
    (net (code "122") (name "/LED_CTRL_40") (class "Default")
      (node (ref "B1") (pin "49") (pinfunction "49_49") (pintype "bidirectional"))
      (node (ref "R45") (pin "P$9") (pinfunction "P$2_P$9") (pintype "passive"))
      (node (ref "R50") (pin "P$8") (pinfunction "P$1_P$8") (pintype "passive"))
    )
    (net (code "123") (name "/LORA_CS") (class "Default")
      (node (ref "B1") (pin "19") (pinfunction "19(RX1)_19") (pintype "bidirectional"))
      (node (ref "U$64") (pin "P$8") (pinfunction "CS_P$8") (pintype "bidirectional"))
    )
    (net (code "124") (name "/LORA_G0") (class "Default")
      (node (ref "B1") (pin "18") (pinfunction "18(TX1)_18") (pintype "bidirectional"))
      (node (ref "U$64") (pin "P$4") (pinfunction "G0_P$4") (pintype "bidirectional"))
    )
    (net (code "125") (name "/LORA_RST") (class "Default")
      (node (ref "B1") (pin "16") (pinfunction "16(TX2)_16") (pintype "bidirectional"))
      (node (ref "U$64") (pin "P$9") (pinfunction "RST_P$9") (pintype "bidirectional"))
    )
    (net (code "126") (name "/MISO") (class "Default")
      (node (ref "B1") (pin "50") (pinfunction "50_50") (pintype "bidirectional"))
      (node (ref "U$64") (pin "P$6") (pinfunction "MISO_P$6") (pintype "bidirectional"))
    )
    (net (code "127") (name "/MOSI") (class "Default")
      (node (ref "B1") (pin "51") (pinfunction "51_51") (pintype "bidirectional"))
      (node (ref "U$64") (pin "P$7") (pinfunction "MOSI_P$7") (pintype "bidirectional"))
    )
    (net (code "128") (name "/RX0") (class "Default")
      (node (ref "B1") (pin "0") (pinfunction "0(RX0)_0") (pintype "bidirectional"))
    )
    (net (code "129") (name "/RX3") (class "Default")
      (node (ref "B1") (pin "15") (pinfunction "15(RX3)_15") (pintype "bidirectional"))
      (node (ref "U$62") (pin "TXO") (pinfunction "P$3_TXO") (pintype "bidirectional"))
    )
    (net (code "130") (name "/SCK") (class "Default")
      (node (ref "B1") (pin "52") (pinfunction "52_52") (pintype "bidirectional"))
      (node (ref "U$64") (pin "P$5") (pinfunction "SCK_P$5") (pintype "bidirectional"))
    )
    (net (code "131") (name "/SCL") (class "Default")
      (node (ref "B1") (pin "21") (pinfunction "21(SCL)_21") (pintype "bidirectional"))
    )
    (net (code "132") (name "/SDA") (class "Default")
      (node (ref "B1") (pin "20") (pinfunction "20(SDA)_20") (pintype "bidirectional"))
    )
    (net (code "133") (name "/SS") (class "Default")
      (node (ref "B1") (pin "53") (pinfunction "53_53") (pintype "bidirectional"))
    )
    (net (code "134") (name "/TX0") (class "Default")
      (node (ref "B1") (pin "1") (pinfunction "1(TX0)_1") (pintype "bidirectional"))
    )
    (net (code "135") (name "/TX3") (class "Default")
      (node (ref "B1") (pin "14") (pinfunction "14(TX3)_14") (pintype "bidirectional"))
      (node (ref "U$62") (pin "RXI") (pinfunction "P$4_RXI") (pintype "bidirectional"))
    )
    (net (code "136") (name "GND") (class "Default")
      (node (ref "B1") (pin "GND@0") (pinfunction "GND_GND@0") (pintype "bidirectional"))
      (node (ref "B1") (pin "GND@1") (pinfunction "GND_GND@1") (pintype "bidirectional"))
      (node (ref "B1") (pin "GND@2") (pinfunction "GND_GND@2") (pintype "bidirectional"))
      (node (ref "B1") (pin "GND@3") (pinfunction "GND_GND@3") (pintype "bidirectional"))
      (node (ref "B1") (pin "GND@4") (pinfunction "GND_GND@4") (pintype "bidirectional"))
      (node (ref "CON5") (pin "2") (pinfunction "P$2_2") (pintype "bidirectional"))
      (node (ref "R41") (pin "P$1") (pinfunction "P$1_P$1") (pintype "passive"))
      (node (ref "R41") (pin "P$2") (pinfunction "P$1_P$2") (pintype "passive"))
      (node (ref "R41") (pin "P$3") (pinfunction "P$1_P$3") (pintype "passive"))
      (node (ref "R41") (pin "P$4") (pinfunction "P$1_P$4") (pintype "passive"))
      (node (ref "R41") (pin "P$5") (pinfunction "P$1_P$5") (pintype "passive"))
      (node (ref "R41") (pin "P$6") (pinfunction "P$1_P$6") (pintype "passive"))
      (node (ref "R41") (pin "P$7") (pinfunction "P$1_P$7") (pintype "passive"))
      (node (ref "R41") (pin "P$8") (pinfunction "P$1_P$8") (pintype "passive"))
      (node (ref "R42") (pin "P$1") (pinfunction "P$1_P$1") (pintype "passive"))
      (node (ref "R42") (pin "P$2") (pinfunction "P$1_P$2") (pintype "passive"))
      (node (ref "R42") (pin "P$3") (pinfunction "P$1_P$3") (pintype "passive"))
      (node (ref "R42") (pin "P$4") (pinfunction "P$1_P$4") (pintype "passive"))
      (node (ref "R42") (pin "P$5") (pinfunction "P$1_P$5") (pintype "passive"))
      (node (ref "R42") (pin "P$6") (pinfunction "P$1_P$6") (pintype "passive"))
      (node (ref "R42") (pin "P$7") (pinfunction "P$1_P$7") (pintype "passive"))
      (node (ref "R42") (pin "P$8") (pinfunction "P$1_P$8") (pintype "passive"))
      (node (ref "R43") (pin "P$1") (pinfunction "P$1_P$1") (pintype "passive"))
      (node (ref "R43") (pin "P$2") (pinfunction "P$1_P$2") (pintype "passive"))
      (node (ref "R43") (pin "P$3") (pinfunction "P$1_P$3") (pintype "passive"))
      (node (ref "R43") (pin "P$4") (pinfunction "P$1_P$4") (pintype "passive"))
      (node (ref "R43") (pin "P$5") (pinfunction "P$1_P$5") (pintype "passive"))
      (node (ref "R43") (pin "P$6") (pinfunction "P$1_P$6") (pintype "passive"))
      (node (ref "R43") (pin "P$7") (pinfunction "P$1_P$7") (pintype "passive"))
      (node (ref "R43") (pin "P$8") (pinfunction "P$1_P$8") (pintype "passive"))
      (node (ref "R44") (pin "P$1") (pinfunction "P$1_P$1") (pintype "passive"))
      (node (ref "R44") (pin "P$2") (pinfunction "P$1_P$2") (pintype "passive"))
      (node (ref "R44") (pin "P$3") (pinfunction "P$1_P$3") (pintype "passive"))
      (node (ref "R44") (pin "P$4") (pinfunction "P$1_P$4") (pintype "passive"))
      (node (ref "R44") (pin "P$5") (pinfunction "P$1_P$5") (pintype "passive"))
      (node (ref "R44") (pin "P$6") (pinfunction "P$1_P$6") (pintype "passive"))
      (node (ref "R44") (pin "P$7") (pinfunction "P$1_P$7") (pintype "passive"))
      (node (ref "R44") (pin "P$8") (pinfunction "P$1_P$8") (pintype "passive"))
      (node (ref "R45") (pin "P$1") (pinfunction "P$1_P$1") (pintype "passive"))
      (node (ref "R45") (pin "P$2") (pinfunction "P$1_P$2") (pintype "passive"))
      (node (ref "R45") (pin "P$3") (pinfunction "P$1_P$3") (pintype "passive"))
      (node (ref "R45") (pin "P$4") (pinfunction "P$1_P$4") (pintype "passive"))
      (node (ref "R45") (pin "P$5") (pinfunction "P$1_P$5") (pintype "passive"))
      (node (ref "R45") (pin "P$6") (pinfunction "P$1_P$6") (pintype "passive"))
      (node (ref "R45") (pin "P$7") (pinfunction "P$1_P$7") (pintype "passive"))
      (node (ref "R45") (pin "P$8") (pinfunction "P$1_P$8") (pintype "passive"))
      (node (ref "U$1") (pin "P$2") (pinfunction "S_P$2") (pintype "output"))
      (node (ref "U$10") (pin "P$2") (pinfunction "S_P$2") (pintype "output"))
      (node (ref "U$15") (pin "P$2") (pinfunction "S_P$2") (pintype "output"))
      (node (ref "U$16") (pin "P$2") (pinfunction "S_P$2") (pintype "output"))
      (node (ref "U$17") (pin "P$2") (pinfunction "S_P$2") (pintype "output"))
      (node (ref "U$18") (pin "P$2") (pinfunction "S_P$2") (pintype "output"))
      (node (ref "U$19") (pin "P$2") (pinfunction "S_P$2") (pintype "output"))
      (node (ref "U$2") (pin "P$2") (pinfunction "S_P$2") (pintype "output"))
      (node (ref "U$20") (pin "P$2") (pinfunction "S_P$2") (pintype "output"))
      (node (ref "U$21") (pin "P$2") (pinfunction "S_P$2") (pintype "output"))
      (node (ref "U$22") (pin "P$2") (pinfunction "S_P$2") (pintype "output"))
      (node (ref "U$27") (pin "P$2") (pinfunction "S_P$2") (pintype "output"))
      (node (ref "U$28") (pin "P$2") (pinfunction "S_P$2") (pintype "output"))
      (node (ref "U$29") (pin "P$2") (pinfunction "S_P$2") (pintype "output"))
      (node (ref "U$3") (pin "P$2") (pinfunction "S_P$2") (pintype "output"))
      (node (ref "U$30") (pin "P$2") (pinfunction "S_P$2") (pintype "output"))
      (node (ref "U$31") (pin "P$2") (pinfunction "S_P$2") (pintype "output"))
      (node (ref "U$32") (pin "P$2") (pinfunction "S_P$2") (pintype "output"))
      (node (ref "U$37") (pin "P$2") (pinfunction "S_P$2") (pintype "output"))
      (node (ref "U$38") (pin "P$2") (pinfunction "S_P$2") (pintype "output"))
      (node (ref "U$39") (pin "P$2") (pinfunction "S_P$2") (pintype "output"))
      (node (ref "U$4") (pin "P$2") (pinfunction "S_P$2") (pintype "output"))
      (node (ref "U$40") (pin "P$2") (pinfunction "S_P$2") (pintype "output"))
      (node (ref "U$41") (pin "P$2") (pinfunction "S_P$2") (pintype "output"))
      (node (ref "U$42") (pin "P$2") (pinfunction "S_P$2") (pintype "output"))
      (node (ref "U$43") (pin "P$2") (pinfunction "S_P$2") (pintype "output"))
      (node (ref "U$44") (pin "P$2") (pinfunction "S_P$2") (pintype "output"))
      (node (ref "U$49") (pin "P$2") (pinfunction "S_P$2") (pintype "output"))
      (node (ref "U$5") (pin "P$2") (pinfunction "S_P$2") (pintype "output"))
      (node (ref "U$50") (pin "P$2") (pinfunction "S_P$2") (pintype "output"))
      (node (ref "U$51") (pin "P$2") (pinfunction "S_P$2") (pintype "output"))
      (node (ref "U$52") (pin "P$2") (pinfunction "S_P$2") (pintype "output"))
      (node (ref "U$53") (pin "P$2") (pinfunction "S_P$2") (pintype "output"))
      (node (ref "U$54") (pin "P$2") (pinfunction "S_P$2") (pintype "output"))
      (node (ref "U$55") (pin "P$2") (pinfunction "S_P$2") (pintype "output"))
      (node (ref "U$56") (pin "P$2") (pinfunction "S_P$2") (pintype "output"))
      (node (ref "U$6") (pin "P$2") (pinfunction "S_P$2") (pintype "output"))
      (node (ref "U$62") (pin "CTS") (pinfunction "P$2_CTS") (pintype "bidirectional"))
      (node (ref "U$62") (pin "GND") (pinfunction "P$7_GND") (pintype "bidirectional"))
      (node (ref "U$64") (pin "P$2") (pinfunction "GND_P$2") (pintype "bidirectional"))
      (node (ref "U$7") (pin "P$2") (pinfunction "S_P$2") (pintype "output"))
      (node (ref "U$8") (pin "P$2") (pinfunction "S_P$2") (pintype "output"))
      (node (ref "U$9") (pin "P$2") (pinfunction "S_P$2") (pintype "output"))
    )
    (net (code "137") (name "Net-(R46A-P$2)") (class "Default")
      (node (ref "R46") (pin "P$16") (pinfunction "P$2_P$16") (pintype "passive"))
      (node (ref "U$3") (pin "P$1") (pinfunction "G_P$1") (pintype "input"))
    )
    (net (code "138") (name "Net-(R46B-P$2)") (class "Default")
      (node (ref "R46") (pin "P$15") (pinfunction "P$2_P$15") (pintype "passive"))
      (node (ref "U$4") (pin "P$1") (pinfunction "G_P$1") (pintype "input"))
    )
    (net (code "139") (name "Net-(R46C-P$2)") (class "Default")
      (node (ref "R46") (pin "P$14") (pinfunction "P$2_P$14") (pintype "passive"))
      (node (ref "U$5") (pin "P$1") (pinfunction "G_P$1") (pintype "input"))
    )
    (net (code "140") (name "Net-(R46D-P$2)") (class "Default")
      (node (ref "R46") (pin "P$13") (pinfunction "P$2_P$13") (pintype "passive"))
      (node (ref "U$6") (pin "P$1") (pinfunction "G_P$1") (pintype "input"))
    )
    (net (code "141") (name "Net-(R46E-P$2)") (class "Default")
      (node (ref "R46") (pin "P$12") (pinfunction "P$2_P$12") (pintype "passive"))
      (node (ref "U$7") (pin "P$1") (pinfunction "G_P$1") (pintype "input"))
    )
    (net (code "142") (name "Net-(R46F-P$2)") (class "Default")
      (node (ref "R46") (pin "P$11") (pinfunction "P$2_P$11") (pintype "passive"))
      (node (ref "U$8") (pin "P$1") (pinfunction "G_P$1") (pintype "input"))
    )
    (net (code "143") (name "Net-(R46G-P$2)") (class "Default")
      (node (ref "R46") (pin "P$10") (pinfunction "P$2_P$10") (pintype "passive"))
      (node (ref "U$9") (pin "P$1") (pinfunction "G_P$1") (pintype "input"))
    )
    (net (code "144") (name "Net-(R46H-P$2)") (class "Default")
      (node (ref "R46") (pin "P$9") (pinfunction "P$2_P$9") (pintype "passive"))
      (node (ref "U$10") (pin "P$1") (pinfunction "G_P$1") (pintype "input"))
    )
    (net (code "145") (name "Net-(R47A-P$2)") (class "Default")
      (node (ref "R47") (pin "P$16") (pinfunction "P$2_P$16") (pintype "passive"))
      (node (ref "U$15") (pin "P$1") (pinfunction "G_P$1") (pintype "input"))
    )
    (net (code "146") (name "Net-(R47B-P$2)") (class "Default")
      (node (ref "R47") (pin "P$15") (pinfunction "P$2_P$15") (pintype "passive"))
      (node (ref "U$16") (pin "P$1") (pinfunction "G_P$1") (pintype "input"))
    )
    (net (code "147") (name "Net-(R47C-P$2)") (class "Default")
      (node (ref "R47") (pin "P$14") (pinfunction "P$2_P$14") (pintype "passive"))
      (node (ref "U$17") (pin "P$1") (pinfunction "G_P$1") (pintype "input"))
    )
    (net (code "148") (name "Net-(R47D-P$2)") (class "Default")
      (node (ref "R47") (pin "P$13") (pinfunction "P$2_P$13") (pintype "passive"))
      (node (ref "U$18") (pin "P$1") (pinfunction "G_P$1") (pintype "input"))
    )
    (net (code "149") (name "Net-(R47E-P$2)") (class "Default")
      (node (ref "R47") (pin "P$12") (pinfunction "P$2_P$12") (pintype "passive"))
      (node (ref "U$19") (pin "P$1") (pinfunction "G_P$1") (pintype "input"))
    )
    (net (code "150") (name "Net-(R47F-P$2)") (class "Default")
      (node (ref "R47") (pin "P$11") (pinfunction "P$2_P$11") (pintype "passive"))
      (node (ref "U$20") (pin "P$1") (pinfunction "G_P$1") (pintype "input"))
    )
    (net (code "151") (name "Net-(R47G-P$2)") (class "Default")
      (node (ref "R47") (pin "P$10") (pinfunction "P$2_P$10") (pintype "passive"))
      (node (ref "U$21") (pin "P$1") (pinfunction "G_P$1") (pintype "input"))
    )
    (net (code "152") (name "Net-(R47H-P$2)") (class "Default")
      (node (ref "R47") (pin "P$9") (pinfunction "P$2_P$9") (pintype "passive"))
      (node (ref "U$22") (pin "P$1") (pinfunction "G_P$1") (pintype "input"))
    )
    (net (code "153") (name "Net-(R48A-P$2)") (class "Default")
      (node (ref "R48") (pin "P$16") (pinfunction "P$2_P$16") (pintype "passive"))
      (node (ref "U$1") (pin "P$1") (pinfunction "G_P$1") (pintype "input"))
    )
    (net (code "154") (name "Net-(R48B-P$2)") (class "Default")
      (node (ref "R48") (pin "P$15") (pinfunction "P$2_P$15") (pintype "passive"))
      (node (ref "U$2") (pin "P$1") (pinfunction "G_P$1") (pintype "input"))
    )
    (net (code "155") (name "Net-(R48C-P$2)") (class "Default")
      (node (ref "R48") (pin "P$14") (pinfunction "P$2_P$14") (pintype "passive"))
      (node (ref "U$27") (pin "P$1") (pinfunction "G_P$1") (pintype "input"))
    )
    (net (code "156") (name "Net-(R48D-P$2)") (class "Default")
      (node (ref "R48") (pin "P$13") (pinfunction "P$2_P$13") (pintype "passive"))
      (node (ref "U$28") (pin "P$1") (pinfunction "G_P$1") (pintype "input"))
    )
    (net (code "157") (name "Net-(R48E-P$2)") (class "Default")
      (node (ref "R48") (pin "P$12") (pinfunction "P$2_P$12") (pintype "passive"))
      (node (ref "U$29") (pin "P$1") (pinfunction "G_P$1") (pintype "input"))
    )
    (net (code "158") (name "Net-(R48F-P$2)") (class "Default")
      (node (ref "R48") (pin "P$11") (pinfunction "P$2_P$11") (pintype "passive"))
      (node (ref "U$30") (pin "P$1") (pinfunction "G_P$1") (pintype "input"))
    )
    (net (code "159") (name "Net-(R48G-P$2)") (class "Default")
      (node (ref "R48") (pin "P$10") (pinfunction "P$2_P$10") (pintype "passive"))
      (node (ref "U$31") (pin "P$1") (pinfunction "G_P$1") (pintype "input"))
    )
    (net (code "160") (name "Net-(R48H-P$2)") (class "Default")
      (node (ref "R48") (pin "P$9") (pinfunction "P$2_P$9") (pintype "passive"))
      (node (ref "U$32") (pin "P$1") (pinfunction "G_P$1") (pintype "input"))
    )
    (net (code "161") (name "Net-(R49A-P$2)") (class "Default")
      (node (ref "R49") (pin "P$16") (pinfunction "P$2_P$16") (pintype "passive"))
      (node (ref "U$37") (pin "P$1") (pinfunction "G_P$1") (pintype "input"))
    )
    (net (code "162") (name "Net-(R49B-P$2)") (class "Default")
      (node (ref "R49") (pin "P$15") (pinfunction "P$2_P$15") (pintype "passive"))
      (node (ref "U$38") (pin "P$1") (pinfunction "G_P$1") (pintype "input"))
    )
    (net (code "163") (name "Net-(R49C-P$2)") (class "Default")
      (node (ref "R49") (pin "P$14") (pinfunction "P$2_P$14") (pintype "passive"))
      (node (ref "U$39") (pin "P$1") (pinfunction "G_P$1") (pintype "input"))
    )
    (net (code "164") (name "Net-(R49D-P$2)") (class "Default")
      (node (ref "R49") (pin "P$13") (pinfunction "P$2_P$13") (pintype "passive"))
      (node (ref "U$40") (pin "P$1") (pinfunction "G_P$1") (pintype "input"))
    )
    (net (code "165") (name "Net-(R49E-P$2)") (class "Default")
      (node (ref "R49") (pin "P$12") (pinfunction "P$2_P$12") (pintype "passive"))
      (node (ref "U$41") (pin "P$1") (pinfunction "G_P$1") (pintype "input"))
    )
    (net (code "166") (name "Net-(R49F-P$2)") (class "Default")
      (node (ref "R49") (pin "P$11") (pinfunction "P$2_P$11") (pintype "passive"))
      (node (ref "U$42") (pin "P$1") (pinfunction "G_P$1") (pintype "input"))
    )
    (net (code "167") (name "Net-(R49G-P$2)") (class "Default")
      (node (ref "R49") (pin "P$10") (pinfunction "P$2_P$10") (pintype "passive"))
      (node (ref "U$43") (pin "P$1") (pinfunction "G_P$1") (pintype "input"))
    )
    (net (code "168") (name "Net-(R49H-P$2)") (class "Default")
      (node (ref "R49") (pin "P$9") (pinfunction "P$2_P$9") (pintype "passive"))
      (node (ref "U$44") (pin "P$1") (pinfunction "G_P$1") (pintype "input"))
    )
    (net (code "169") (name "Net-(R50A-P$2)") (class "Default")
      (node (ref "R50") (pin "P$16") (pinfunction "P$2_P$16") (pintype "passive"))
      (node (ref "U$49") (pin "P$1") (pinfunction "G_P$1") (pintype "input"))
    )
    (net (code "170") (name "Net-(R50B-P$2)") (class "Default")
      (node (ref "R50") (pin "P$15") (pinfunction "P$2_P$15") (pintype "passive"))
      (node (ref "U$50") (pin "P$1") (pinfunction "G_P$1") (pintype "input"))
    )
    (net (code "171") (name "Net-(R50C-P$2)") (class "Default")
      (node (ref "R50") (pin "P$14") (pinfunction "P$2_P$14") (pintype "passive"))
      (node (ref "U$51") (pin "P$1") (pinfunction "G_P$1") (pintype "input"))
    )
    (net (code "172") (name "Net-(R50D-P$2)") (class "Default")
      (node (ref "R50") (pin "P$13") (pinfunction "P$2_P$13") (pintype "passive"))
      (node (ref "U$52") (pin "P$1") (pinfunction "G_P$1") (pintype "input"))
    )
    (net (code "173") (name "Net-(R50E-P$2)") (class "Default")
      (node (ref "R50") (pin "P$12") (pinfunction "P$2_P$12") (pintype "passive"))
      (node (ref "U$53") (pin "P$1") (pinfunction "G_P$1") (pintype "input"))
    )
    (net (code "174") (name "Net-(R50F-P$2)") (class "Default")
      (node (ref "R50") (pin "P$11") (pinfunction "P$2_P$11") (pintype "passive"))
      (node (ref "U$54") (pin "P$1") (pinfunction "G_P$1") (pintype "input"))
    )
    (net (code "175") (name "Net-(R50G-P$2)") (class "Default")
      (node (ref "R50") (pin "P$10") (pinfunction "P$2_P$10") (pintype "passive"))
      (node (ref "U$55") (pin "P$1") (pinfunction "G_P$1") (pintype "input"))
    )
    (net (code "176") (name "Net-(R50H-P$2)") (class "Default")
      (node (ref "R50") (pin "P$9") (pinfunction "P$2_P$9") (pintype "passive"))
      (node (ref "U$56") (pin "P$1") (pinfunction "G_P$1") (pintype "input"))
    )
    (net (code "177") (name "Net-(U$62-P$5)") (class "Default")
      (node (ref "B1") (pin "5V@0") (pinfunction "5V_5V@0") (pintype "bidirectional"))
      (node (ref "U$62") (pin "VIN") (pinfunction "P$5_VIN") (pintype "bidirectional"))
      (node (ref "U$64") (pin "P$1") (pinfunction "VIN_P$1") (pintype "bidirectional"))
    )
    (net (code "178") (name "Net-(U$62-P$8)") (class "Default")
      (node (ref "B1") (pin "A8") (pinfunction "A8_A8") (pintype "bidirectional"))
      (node (ref "U$62") (pin "DFU") (pinfunction "P$8_DFU") (pintype "bidirectional"))
    )
    (net (code "179") (name "unconnected-(B1-5V-Pad5V@1)") (class "Default")
      (node (ref "B1") (pin "5V@1") (pinfunction "5V_5V@1") (pintype "bidirectional"))
    )
    (net (code "180") (name "unconnected-(B1-5V-Pad5V@2)") (class "Default")
      (node (ref "B1") (pin "5V@2") (pinfunction "5V_5V@2") (pintype "bidirectional"))
    )
    (net (code "181") (name "unconnected-(B1-A0(RX0)-PadA0)") (class "Default")
      (node (ref "B1") (pin "A0") (pinfunction "A0(RX0)_A0") (pintype "bidirectional"))
    )
    (net (code "182") (name "unconnected-(B1-A1(TX0)-PadA1)") (class "Default")
      (node (ref "B1") (pin "A1") (pinfunction "A1(TX0)_A1") (pintype "bidirectional"))
    )
    (net (code "183") (name "unconnected-(B1-Pad3.3V)") (class "Default")
      (node (ref "B1") (pin "3.3V") (pinfunction "3.3V_3.3V") (pintype "bidirectional"))
    )
    (net (code "184") (name "unconnected-(B1-PadA2)") (class "Default")
      (node (ref "B1") (pin "A2") (pinfunction "A2_A2") (pintype "bidirectional"))
    )
    (net (code "185") (name "unconnected-(B1-PadA3)") (class "Default")
      (node (ref "B1") (pin "A3") (pinfunction "A3_A3") (pintype "bidirectional"))
    )
    (net (code "186") (name "unconnected-(B1-PadA4)") (class "Default")
      (node (ref "B1") (pin "A4") (pinfunction "A4_A4") (pintype "bidirectional"))
    )
    (net (code "187") (name "unconnected-(B1-PadA5)") (class "Default")
      (node (ref "B1") (pin "A5") (pinfunction "A5_A5") (pintype "bidirectional"))
    )
    (net (code "188") (name "unconnected-(B1-PadA6)") (class "Default")
      (node (ref "B1") (pin "A6") (pinfunction "A6_A6") (pintype "bidirectional"))
    )
    (net (code "189") (name "unconnected-(B1-PadA7)") (class "Default")
      (node (ref "B1") (pin "A7") (pinfunction "A7_A7") (pintype "bidirectional"))
    )
    (net (code "190") (name "unconnected-(B1-PadA9)") (class "Default")
      (node (ref "B1") (pin "A9") (pinfunction "A9_A9") (pintype "bidirectional"))
    )
    (net (code "191") (name "unconnected-(B1-PadA10)") (class "Default")
      (node (ref "B1") (pin "A10") (pinfunction "A10_A10") (pintype "bidirectional"))
    )
    (net (code "192") (name "unconnected-(B1-PadA11)") (class "Default")
      (node (ref "B1") (pin "A11") (pinfunction "A11_A11") (pintype "bidirectional"))
    )
    (net (code "193") (name "unconnected-(B1-PadA12)") (class "Default")
      (node (ref "B1") (pin "A12") (pinfunction "A12_A12") (pintype "bidirectional"))
    )
    (net (code "194") (name "unconnected-(B1-PadA13)") (class "Default")
      (node (ref "B1") (pin "A13") (pinfunction "A13_A13") (pintype "bidirectional"))
    )
    (net (code "195") (name "unconnected-(B1-PadA14)") (class "Default")
      (node (ref "B1") (pin "A14") (pinfunction "A14_A14") (pintype "bidirectional"))
    )
    (net (code "196") (name "unconnected-(B1-PadA15)") (class "Default")
      (node (ref "B1") (pin "A15") (pinfunction "A15_A15") (pintype "bidirectional"))
    )
    (net (code "197") (name "unconnected-(B1-PadAREF)") (class "Default")
      (node (ref "B1") (pin "AREF") (pinfunction "AREF_AREF") (pintype "bidirectional"))
    )
    (net (code "198") (name "unconnected-(B1-PadRESET)") (class "Default")
      (node (ref "B1") (pin "RESET") (pinfunction "RESET_RESET") (pintype "bidirectional"))
    )
    (net (code "199") (name "unconnected-(B1-PadVIN)") (class "Default")
      (node (ref "B1") (pin "VIN") (pinfunction "VIN_VIN") (pintype "bidirectional"))
    )
    (net (code "200") (name "unconnected-(U$62-P$6-PadRTS)") (class "Default")
      (node (ref "U$62") (pin "RTS") (pinfunction "P$6_RTS") (pintype "bidirectional"))
    )
    (net (code "201") (name "unconnected-(U$64-EN-PadP$3)") (class "Default")
      (node (ref "U$64") (pin "P$3") (pinfunction "EN_P$3") (pintype "bidirectional"))
    )
    (net (code "202") (name "unconnected-(U$64-G1-PadP$10)") (class "Default")
      (node (ref "U$64") (pin "P$10") (pinfunction "G1_P$10") (pintype "bidirectional"))
    )
    (net (code "203") (name "unconnected-(U$64-G2-PadP$11)") (class "Default")
      (node (ref "U$64") (pin "P$11") (pinfunction "G2_P$11") (pintype "bidirectional"))
    )
    (net (code "204") (name "unconnected-(U$64-G3-PadP$12)") (class "Default")
      (node (ref "U$64") (pin "P$12") (pinfunction "G3_P$12") (pintype "bidirectional"))
    )
    (net (code "205") (name "unconnected-(U$64-G4-PadP$13)") (class "Default")
      (node (ref "U$64") (pin "P$13") (pinfunction "G4_P$13") (pintype "bidirectional"))
    )
    (net (code "206") (name "unconnected-(U$64-G5-PadP$14)") (class "Default")
      (node (ref "U$64") (pin "P$14") (pinfunction "G5_P$14") (pintype "bidirectional"))
    )
  )
)
